# SCH_Portable-PDS-DIMM-Card-Rev-1_1_2026-.net
KiCad netlist of a schematic drawn in EasyEDA
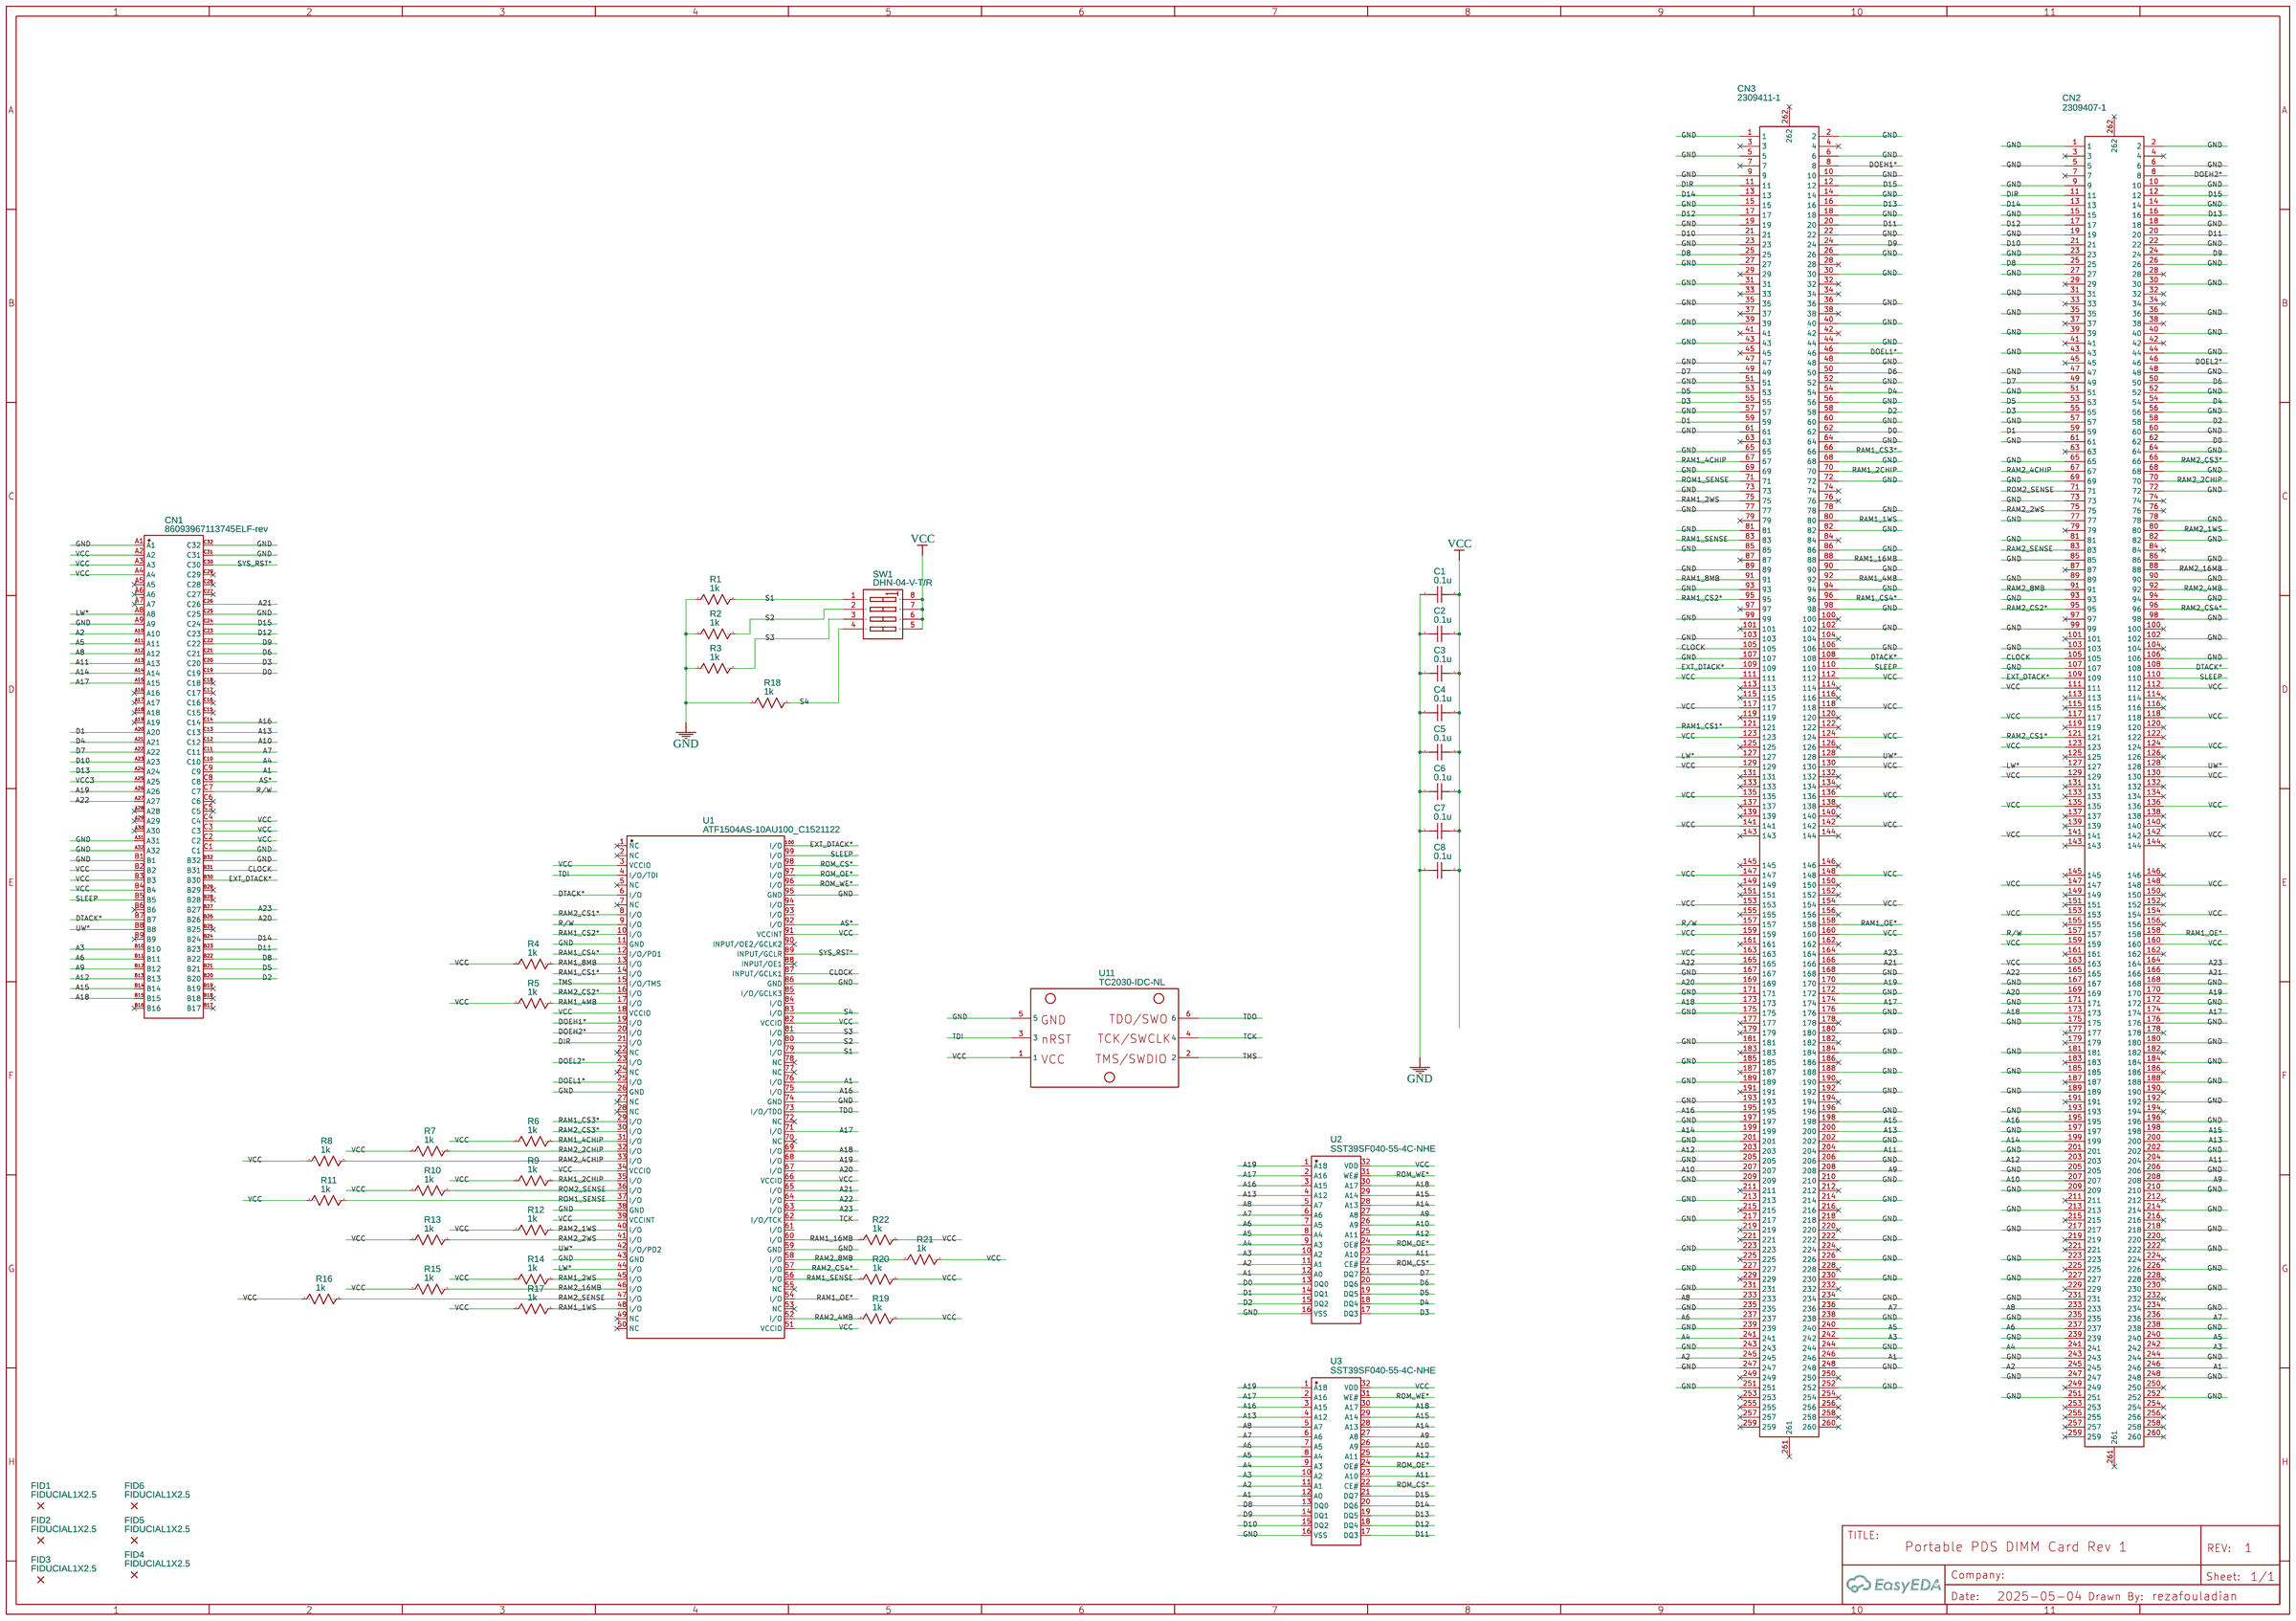
[diagram p0: schematic sheet]

(export (version "E")
  (design (tool "Eeschema 10.0.6"))
  (components
    (comp (ref "C1") (value "0.1u") (libsource (lib "") (part "C_0402_US")))
    (comp (ref "C2") (value "0.1u") (libsource (lib "") (part "C_0402_US")))
    (comp (ref "C3") (value "0.1u") (libsource (lib "") (part "C_0402_US")))
    (comp (ref "C4") (value "0.1u") (libsource (lib "") (part "C_0402_US")))
    (comp (ref "C5") (value "0.1u") (libsource (lib "") (part "C_0402_US")))
    (comp (ref "C6") (value "0.1u") (libsource (lib "") (part "C_0402_US")))
    (comp (ref "C7") (value "0.1u") (libsource (lib "") (part "C_0402_US")))
    (comp (ref "C8") (value "0.1u") (libsource (lib "") (part "C_0402_US")))
    (comp (ref "CN1")
      (value "86093967113745ELF-rev")
      (fields (field (name "Manufacturer Part") "86093967113745ELF") (field (name "Manufacturer") "Amphenol"))
      (libsource (lib "") (part "86093967113745ELF-rev"))
    )
    (comp (ref "CN2")
      (value "2309407-1")
      (fields (field (name "Manufacturer") "TE Connectivity(泰科电子)"))
      (libsource (lib "") (part "2309407-1"))
    )
    (comp (ref "CN3")
      (value "2309411-1")
      (fields (field (name "Manufacturer") "TE Connectivity(泰科电子)"))
      (libsource (lib "") (part "2309411-1"))
    )
    (comp (ref "FID1") (value "FIDUCIAL1X2.5") (libsource (lib "") (part "FIDUCIAL1X2.5")))
    (comp (ref "FID2") (value "FIDUCIAL1X2.5") (libsource (lib "") (part "FIDUCIAL1X2.5")))
    (comp (ref "FID3") (value "FIDUCIAL1X2.5") (libsource (lib "") (part "FIDUCIAL1X2.5")))
    (comp (ref "FID4") (value "FIDUCIAL1X2.5") (libsource (lib "") (part "FIDUCIAL1X2.5")))
    (comp (ref "FID5") (value "FIDUCIAL1X2.5") (libsource (lib "") (part "FIDUCIAL1X2.5")))
    (comp (ref "FID6") (value "FIDUCIAL1X2.5") (libsource (lib "") (part "FIDUCIAL1X2.5")))
    (comp (ref "OSHW")
      (value "OSHWA LOGO")
      (fields (field (name "Manufacturer") "Open Source Hardware Association"))
      (libsource (lib "") (part "OSHWA LOGO"))
    )
    (comp (ref "R1") (value "1k") (libsource (lib "") (part "R_0402_US")))
    (comp (ref "R2") (value "1k") (libsource (lib "") (part "R_0402_US")))
    (comp (ref "R3") (value "1k") (libsource (lib "") (part "R_0402_US")))
    (comp (ref "R4") (value "1k") (libsource (lib "") (part "R_0402_US")))
    (comp (ref "R5") (value "1k") (libsource (lib "") (part "R_0402_US")))
    (comp (ref "R6") (value "1k") (libsource (lib "") (part "R_0402_US")))
    (comp (ref "R7") (value "1k") (libsource (lib "") (part "R_0402_US")))
    (comp (ref "R8") (value "1k") (libsource (lib "") (part "R_0402_US")))
    (comp (ref "R9") (value "1k") (libsource (lib "") (part "R_0402_US")))
    (comp (ref "R10") (value "1k") (libsource (lib "") (part "R_0402_US")))
    (comp (ref "R11") (value "1k") (libsource (lib "") (part "R_0402_US")))
    (comp (ref "R12") (value "1k") (libsource (lib "") (part "R_0402_US")))
    (comp (ref "R13") (value "1k") (libsource (lib "") (part "R_0402_US")))
    (comp (ref "R14") (value "1k") (libsource (lib "") (part "R_0402_US")))
    (comp (ref "R15") (value "1k") (libsource (lib "") (part "R_0402_US")))
    (comp (ref "R16") (value "1k") (libsource (lib "") (part "R_0402_US")))
    (comp (ref "R17") (value "1k") (libsource (lib "") (part "R_0402_US")))
    (comp (ref "R18") (value "1k") (libsource (lib "") (part "R_0402_US")))
    (comp (ref "R19") (value "1k") (libsource (lib "") (part "R_0402_US")))
    (comp (ref "R20") (value "1k") (libsource (lib "") (part "R_0402_US")))
    (comp (ref "R21") (value "1k") (libsource (lib "") (part "R_0402_US")))
    (comp (ref "R22") (value "1k") (libsource (lib "") (part "R_0402_US")))
    (comp (ref "SW1")
      (value "DHN-04-V-T/R")
      (fields (field (name "Manufacturer") "圜达"))
      (libsource (lib "") (part "DHN-04-V-T/R"))
    )
    (comp (ref "U1")
      (value "ATF1504AS-10AU100_C1521122")
      (fields
        (field (name "Manufacturer Part") "ATF1504AS-10AU100")
        (field (name "Manufacturer") "MICROCHIP(美国微芯)")
      )
      (libsource (lib "") (part "ATF1504AS-10AU100_C1521122"))
    )
    (comp (ref "U2")
      (value "SST39SF040-55-4C-NHE")
      (fields (field (name "Manufacturer") "MICROCHIP(美国微芯)"))
      (libsource (lib "") (part "SST39SF040-55-4C-NHE"))
    )
    (comp (ref "U3")
      (value "SST39SF040-55-4C-NHE")
      (fields (field (name "Manufacturer") "MICROCHIP(美国微芯)"))
      (libsource (lib "") (part "SST39SF040-55-4C-NHE"))
    )
    (comp (ref "U11")
      (value "TC2030-IDC-NL")
      (fields (field (name "Manufacturer") "Tag-Connect"))
      (libsource (lib "") (part "TC2030-IDC-NL"))
    )
  )
  (nets
    (net (code "1") (name "/A1") (class "Default")
      (node (ref "CN1") (pin "C9") (pinfunction "C9_C9") (pintype "unspecified"))
      (node (ref "CN2") (pin "246") (pinfunction "246_246") (pintype "unspecified"))
      (node (ref "CN3") (pin "246") (pinfunction "246_246") (pintype "unspecified"))
      (node (ref "U1") (pin "76") (pinfunction "I/O_76") (pintype "unspecified"))
      (node (ref "U2") (pin "12") (pinfunction "A0_12") (pintype "unspecified"))
      (node (ref "U3") (pin "12") (pinfunction "A0_12") (pintype "unspecified"))
    )
    (net (code "2") (name "/A2") (class "Default")
      (node (ref "CN1") (pin "A10") (pinfunction "A10_A10") (pintype "unspecified"))
      (node (ref "CN2") (pin "245") (pinfunction "245_245") (pintype "unspecified"))
      (node (ref "CN3") (pin "245") (pinfunction "245_245") (pintype "unspecified"))
      (node (ref "U2") (pin "11") (pinfunction "A1_11") (pintype "unspecified"))
      (node (ref "U3") (pin "11") (pinfunction "A1_11") (pintype "unspecified"))
    )
    (net (code "3") (name "/A3") (class "Default")
      (node (ref "CN1") (pin "B10") (pinfunction "B10_B10") (pintype "unspecified"))
      (node (ref "CN2") (pin "242") (pinfunction "242_242") (pintype "unspecified"))
      (node (ref "CN3") (pin "242") (pinfunction "242_242") (pintype "unspecified"))
      (node (ref "U2") (pin "10") (pinfunction "A2_10") (pintype "unspecified"))
      (node (ref "U3") (pin "10") (pinfunction "A2_10") (pintype "unspecified"))
    )
    (net (code "4") (name "/A4") (class "Default")
      (node (ref "CN1") (pin "C10") (pinfunction "C10_C10") (pintype "unspecified"))
      (node (ref "CN2") (pin "241") (pinfunction "241_241") (pintype "unspecified"))
      (node (ref "CN3") (pin "241") (pinfunction "241_241") (pintype "unspecified"))
      (node (ref "U2") (pin "9") (pinfunction "A3_9") (pintype "unspecified"))
      (node (ref "U3") (pin "9") (pinfunction "A3_9") (pintype "unspecified"))
    )
    (net (code "5") (name "/A5") (class "Default")
      (node (ref "CN1") (pin "A11") (pinfunction "A11_A11") (pintype "unspecified"))
      (node (ref "CN2") (pin "240") (pinfunction "240_240") (pintype "unspecified"))
      (node (ref "CN3") (pin "240") (pinfunction "240_240") (pintype "unspecified"))
      (node (ref "U2") (pin "8") (pinfunction "A4_8") (pintype "unspecified"))
      (node (ref "U3") (pin "8") (pinfunction "A4_8") (pintype "unspecified"))
    )
    (net (code "6") (name "/A6") (class "Default")
      (node (ref "CN1") (pin "B11") (pinfunction "B11_B11") (pintype "unspecified"))
      (node (ref "CN2") (pin "237") (pinfunction "237_237") (pintype "unspecified"))
      (node (ref "CN3") (pin "237") (pinfunction "237_237") (pintype "unspecified"))
      (node (ref "U2") (pin "7") (pinfunction "A5_7") (pintype "unspecified"))
      (node (ref "U3") (pin "7") (pinfunction "A5_7") (pintype "unspecified"))
    )
    (net (code "7") (name "/A7") (class "Default")
      (node (ref "CN1") (pin "C11") (pinfunction "C11_C11") (pintype "unspecified"))
      (node (ref "CN2") (pin "236") (pinfunction "236_236") (pintype "unspecified"))
      (node (ref "CN3") (pin "236") (pinfunction "236_236") (pintype "unspecified"))
      (node (ref "U2") (pin "6") (pinfunction "A6_6") (pintype "unspecified"))
      (node (ref "U3") (pin "6") (pinfunction "A6_6") (pintype "unspecified"))
    )
    (net (code "8") (name "/A8") (class "Default")
      (node (ref "CN1") (pin "A12") (pinfunction "A12_A12") (pintype "unspecified"))
      (node (ref "CN2") (pin "233") (pinfunction "233_233") (pintype "unspecified"))
      (node (ref "CN3") (pin "233") (pinfunction "233_233") (pintype "unspecified"))
      (node (ref "U2") (pin "5") (pinfunction "A7_5") (pintype "unspecified"))
      (node (ref "U3") (pin "5") (pinfunction "A7_5") (pintype "unspecified"))
    )
    (net (code "9") (name "/A9") (class "Default")
      (node (ref "CN1") (pin "B12") (pinfunction "B12_B12") (pintype "unspecified"))
      (node (ref "CN2") (pin "208") (pinfunction "208_208") (pintype "unspecified"))
      (node (ref "CN3") (pin "208") (pinfunction "208_208") (pintype "unspecified"))
      (node (ref "U2") (pin "27") (pinfunction "A8_27") (pintype "unspecified"))
      (node (ref "U3") (pin "27") (pinfunction "A8_27") (pintype "unspecified"))
    )
    (net (code "10") (name "/A10") (class "Default")
      (node (ref "CN1") (pin "C12") (pinfunction "C12_C12") (pintype "unspecified"))
      (node (ref "CN2") (pin "207") (pinfunction "207_207") (pintype "unspecified"))
      (node (ref "CN3") (pin "207") (pinfunction "207_207") (pintype "unspecified"))
      (node (ref "U2") (pin "26") (pinfunction "A9_26") (pintype "unspecified"))
      (node (ref "U3") (pin "26") (pinfunction "A9_26") (pintype "unspecified"))
    )
    (net (code "11") (name "/A11") (class "Default")
      (node (ref "CN1") (pin "A13") (pinfunction "A13_A13") (pintype "unspecified"))
      (node (ref "CN2") (pin "204") (pinfunction "204_204") (pintype "unspecified"))
      (node (ref "CN3") (pin "204") (pinfunction "204_204") (pintype "unspecified"))
      (node (ref "U2") (pin "23") (pinfunction "A10_23") (pintype "unspecified"))
      (node (ref "U3") (pin "23") (pinfunction "A10_23") (pintype "unspecified"))
    )
    (net (code "12") (name "/A12") (class "Default")
      (node (ref "CN1") (pin "B13") (pinfunction "B13_B13") (pintype "unspecified"))
      (node (ref "CN2") (pin "203") (pinfunction "203_203") (pintype "unspecified"))
      (node (ref "CN3") (pin "203") (pinfunction "203_203") (pintype "unspecified"))
      (node (ref "U2") (pin "25") (pinfunction "A11_25") (pintype "unspecified"))
      (node (ref "U3") (pin "25") (pinfunction "A11_25") (pintype "unspecified"))
    )
    (net (code "13") (name "/A13") (class "Default")
      (node (ref "CN1") (pin "C13") (pinfunction "C13_C13") (pintype "unspecified"))
      (node (ref "CN2") (pin "200") (pinfunction "200_200") (pintype "unspecified"))
      (node (ref "CN3") (pin "200") (pinfunction "200_200") (pintype "unspecified"))
      (node (ref "U2") (pin "4") (pinfunction "A12_4") (pintype "unspecified"))
      (node (ref "U3") (pin "4") (pinfunction "A12_4") (pintype "unspecified"))
    )
    (net (code "14") (name "/A14") (class "Default")
      (node (ref "CN1") (pin "A14") (pinfunction "A14_A14") (pintype "unspecified"))
      (node (ref "CN2") (pin "199") (pinfunction "199_199") (pintype "unspecified"))
      (node (ref "CN3") (pin "199") (pinfunction "199_199") (pintype "unspecified"))
      (node (ref "U2") (pin "28") (pinfunction "A13_28") (pintype "unspecified"))
      (node (ref "U3") (pin "28") (pinfunction "A13_28") (pintype "unspecified"))
    )
    (net (code "15") (name "/A15") (class "Default")
      (node (ref "CN1") (pin "B14") (pinfunction "B14_B14") (pintype "unspecified"))
      (node (ref "CN2") (pin "198") (pinfunction "198_198") (pintype "unspecified"))
      (node (ref "CN3") (pin "198") (pinfunction "198_198") (pintype "unspecified"))
      (node (ref "U2") (pin "29") (pinfunction "A14_29") (pintype "unspecified"))
      (node (ref "U3") (pin "29") (pinfunction "A14_29") (pintype "unspecified"))
    )
    (net (code "16") (name "/A16") (class "Default")
      (node (ref "CN1") (pin "C14") (pinfunction "C14_C14") (pintype "unspecified"))
      (node (ref "CN2") (pin "195") (pinfunction "195_195") (pintype "unspecified"))
      (node (ref "CN3") (pin "195") (pinfunction "195_195") (pintype "unspecified"))
      (node (ref "U1") (pin "75") (pinfunction "I/O_75") (pintype "unspecified"))
      (node (ref "U2") (pin "3") (pinfunction "A15_3") (pintype "unspecified"))
      (node (ref "U3") (pin "3") (pinfunction "A15_3") (pintype "unspecified"))
    )
    (net (code "17") (name "/A17") (class "Default")
      (node (ref "CN1") (pin "A15") (pinfunction "A15_A15") (pintype "unspecified"))
      (node (ref "CN2") (pin "174") (pinfunction "174_174") (pintype "unspecified"))
      (node (ref "CN3") (pin "174") (pinfunction "174_174") (pintype "unspecified"))
      (node (ref "U1") (pin "71") (pinfunction "I/O_71") (pintype "unspecified"))
      (node (ref "U2") (pin "2") (pinfunction "A16_2") (pintype "unspecified"))
      (node (ref "U3") (pin "2") (pinfunction "A16_2") (pintype "unspecified"))
    )
    (net (code "18") (name "/A18") (class "Default")
      (node (ref "CN1") (pin "B15") (pinfunction "B15_B15") (pintype "unspecified"))
      (node (ref "CN2") (pin "173") (pinfunction "173_173") (pintype "unspecified"))
      (node (ref "CN3") (pin "173") (pinfunction "173_173") (pintype "unspecified"))
      (node (ref "U1") (pin "69") (pinfunction "I/O_69") (pintype "unspecified"))
      (node (ref "U2") (pin "30") (pinfunction "A17_30") (pintype "unspecified"))
      (node (ref "U3") (pin "30") (pinfunction "A17_30") (pintype "unspecified"))
    )
    (net (code "19") (name "/A19") (class "Default")
      (node (ref "CN1") (pin "A26") (pinfunction "A26_A26") (pintype "unspecified"))
      (node (ref "CN2") (pin "170") (pinfunction "170_170") (pintype "unspecified"))
      (node (ref "CN3") (pin "170") (pinfunction "170_170") (pintype "unspecified"))
      (node (ref "U1") (pin "68") (pinfunction "I/O_68") (pintype "unspecified"))
      (node (ref "U2") (pin "1") (pinfunction "A18_1") (pintype "unspecified"))
      (node (ref "U3") (pin "1") (pinfunction "A18_1") (pintype "unspecified"))
    )
    (net (code "20") (name "/A20") (class "Default")
      (node (ref "CN1") (pin "B26") (pinfunction "B26_B26") (pintype "unspecified"))
      (node (ref "CN2") (pin "169") (pinfunction "169_169") (pintype "unspecified"))
      (node (ref "CN3") (pin "169") (pinfunction "169_169") (pintype "unspecified"))
      (node (ref "U1") (pin "67") (pinfunction "I/O_67") (pintype "unspecified"))
    )
    (net (code "21") (name "/A21") (class "Default")
      (node (ref "CN1") (pin "C26") (pinfunction "C26_C26") (pintype "unspecified"))
      (node (ref "CN2") (pin "166") (pinfunction "166_166") (pintype "unspecified"))
      (node (ref "CN3") (pin "166") (pinfunction "166_166") (pintype "unspecified"))
      (node (ref "U1") (pin "65") (pinfunction "I/O_65") (pintype "unspecified"))
    )
    (net (code "22") (name "/A22") (class "Default")
      (node (ref "CN1") (pin "A27") (pinfunction "A27_A27") (pintype "unspecified"))
      (node (ref "CN2") (pin "165") (pinfunction "165_165") (pintype "unspecified"))
      (node (ref "CN3") (pin "165") (pinfunction "165_165") (pintype "unspecified"))
      (node (ref "U1") (pin "64") (pinfunction "I/O_64") (pintype "unspecified"))
    )
    (net (code "23") (name "/A23") (class "Default")
      (node (ref "CN1") (pin "B27") (pinfunction "B27_B27") (pintype "unspecified"))
      (node (ref "CN2") (pin "164") (pinfunction "164_164") (pintype "unspecified"))
      (node (ref "CN3") (pin "164") (pinfunction "164_164") (pintype "unspecified"))
      (node (ref "U1") (pin "63") (pinfunction "I/O_63") (pintype "unspecified"))
    )
    (net (code "24") (name "/AS*") (class "Default")
      (node (ref "CN1") (pin "C8") (pinfunction "C8_C8") (pintype "unspecified"))
      (node (ref "U1") (pin "92") (pinfunction "I/O_92") (pintype "unspecified"))
    )
    (net (code "25") (name "/CLOCK") (class "Default")
      (node (ref "CN1") (pin "B31") (pinfunction "B31_B31") (pintype "unspecified"))
      (node (ref "CN2") (pin "105") (pinfunction "105_105") (pintype "unspecified"))
      (node (ref "CN3") (pin "105") (pinfunction "105_105") (pintype "unspecified"))
      (node (ref "U1") (pin "87") (pinfunction "INPUT/GCLK1_87") (pintype "unspecified"))
    )
    (net (code "26") (name "/D0") (class "Default")
      (node (ref "CN1") (pin "C19") (pinfunction "C19_C19") (pintype "unspecified"))
      (node (ref "CN2") (pin "62") (pinfunction "62_62") (pintype "unspecified"))
      (node (ref "CN3") (pin "62") (pinfunction "62_62") (pintype "unspecified"))
      (node (ref "U2") (pin "13") (pinfunction "DQ0_13") (pintype "unspecified"))
    )
    (net (code "27") (name "/D1") (class "Default")
      (node (ref "CN1") (pin "A20") (pinfunction "A20_A20") (pintype "unspecified"))
      (node (ref "CN2") (pin "59") (pinfunction "59_59") (pintype "unspecified"))
      (node (ref "CN3") (pin "59") (pinfunction "59_59") (pintype "unspecified"))
      (node (ref "U2") (pin "14") (pinfunction "DQ1_14") (pintype "unspecified"))
    )
    (net (code "28") (name "/D2") (class "Default")
      (node (ref "CN1") (pin "B20") (pinfunction "B20_B20") (pintype "unspecified"))
      (node (ref "CN2") (pin "58") (pinfunction "58_58") (pintype "unspecified"))
      (node (ref "CN3") (pin "58") (pinfunction "58_58") (pintype "unspecified"))
      (node (ref "U2") (pin "15") (pinfunction "DQ2_15") (pintype "unspecified"))
    )
    (net (code "29") (name "/D3") (class "Default")
      (node (ref "CN1") (pin "C20") (pinfunction "C20_C20") (pintype "unspecified"))
      (node (ref "CN2") (pin "55") (pinfunction "55_55") (pintype "unspecified"))
      (node (ref "CN3") (pin "55") (pinfunction "55_55") (pintype "unspecified"))
      (node (ref "U2") (pin "17") (pinfunction "DQ3_17") (pintype "unspecified"))
    )
    (net (code "30") (name "/D4") (class "Default")
      (node (ref "CN1") (pin "A21") (pinfunction "A21_A21") (pintype "unspecified"))
      (node (ref "CN2") (pin "54") (pinfunction "54_54") (pintype "unspecified"))
      (node (ref "CN3") (pin "54") (pinfunction "54_54") (pintype "unspecified"))
      (node (ref "U2") (pin "18") (pinfunction "DQ4_18") (pintype "unspecified"))
    )
    (net (code "31") (name "/D5") (class "Default")
      (node (ref "CN1") (pin "B21") (pinfunction "B21_B21") (pintype "unspecified"))
      (node (ref "CN2") (pin "53") (pinfunction "53_53") (pintype "unspecified"))
      (node (ref "CN3") (pin "53") (pinfunction "53_53") (pintype "unspecified"))
      (node (ref "U2") (pin "19") (pinfunction "DQ5_19") (pintype "unspecified"))
    )
    (net (code "32") (name "/D6") (class "Default")
      (node (ref "CN1") (pin "C21") (pinfunction "C21_C21") (pintype "unspecified"))
      (node (ref "CN2") (pin "50") (pinfunction "50_50") (pintype "unspecified"))
      (node (ref "CN3") (pin "50") (pinfunction "50_50") (pintype "unspecified"))
      (node (ref "U2") (pin "20") (pinfunction "DQ6_20") (pintype "unspecified"))
    )
    (net (code "33") (name "/D7") (class "Default")
      (node (ref "CN1") (pin "A22") (pinfunction "A22_A22") (pintype "unspecified"))
      (node (ref "CN2") (pin "49") (pinfunction "49_49") (pintype "unspecified"))
      (node (ref "CN3") (pin "49") (pinfunction "49_49") (pintype "unspecified"))
      (node (ref "U2") (pin "21") (pinfunction "DQ7_21") (pintype "unspecified"))
    )
    (net (code "34") (name "/D8") (class "Default")
      (node (ref "CN1") (pin "B22") (pinfunction "B22_B22") (pintype "unspecified"))
      (node (ref "CN2") (pin "25") (pinfunction "25_25") (pintype "unspecified"))
      (node (ref "CN3") (pin "25") (pinfunction "25_25") (pintype "unspecified"))
      (node (ref "U3") (pin "13") (pinfunction "DQ0_13") (pintype "unspecified"))
    )
    (net (code "35") (name "/D9") (class "Default")
      (node (ref "CN1") (pin "C22") (pinfunction "C22_C22") (pintype "unspecified"))
      (node (ref "CN2") (pin "24") (pinfunction "24_24") (pintype "unspecified"))
      (node (ref "CN3") (pin "24") (pinfunction "24_24") (pintype "unspecified"))
      (node (ref "U3") (pin "14") (pinfunction "DQ1_14") (pintype "unspecified"))
    )
    (net (code "36") (name "/D10") (class "Default")
      (node (ref "CN1") (pin "A23") (pinfunction "A23_A23") (pintype "unspecified"))
      (node (ref "CN2") (pin "21") (pinfunction "21_21") (pintype "unspecified"))
      (node (ref "CN3") (pin "21") (pinfunction "21_21") (pintype "unspecified"))
      (node (ref "U3") (pin "15") (pinfunction "DQ2_15") (pintype "unspecified"))
    )
    (net (code "37") (name "/D11") (class "Default")
      (node (ref "CN1") (pin "B23") (pinfunction "B23_B23") (pintype "unspecified"))
      (node (ref "CN2") (pin "20") (pinfunction "20_20") (pintype "unspecified"))
      (node (ref "CN3") (pin "20") (pinfunction "20_20") (pintype "unspecified"))
      (node (ref "U3") (pin "17") (pinfunction "DQ3_17") (pintype "unspecified"))
    )
    (net (code "38") (name "/D12") (class "Default")
      (node (ref "CN1") (pin "C23") (pinfunction "C23_C23") (pintype "unspecified"))
      (node (ref "CN2") (pin "17") (pinfunction "17_17") (pintype "unspecified"))
      (node (ref "CN3") (pin "17") (pinfunction "17_17") (pintype "unspecified"))
      (node (ref "U3") (pin "18") (pinfunction "DQ4_18") (pintype "unspecified"))
    )
    (net (code "39") (name "/D13") (class "Default")
      (node (ref "CN1") (pin "A24") (pinfunction "A24_A24") (pintype "unspecified"))
      (node (ref "CN2") (pin "16") (pinfunction "16_16") (pintype "unspecified"))
      (node (ref "CN3") (pin "16") (pinfunction "16_16") (pintype "unspecified"))
      (node (ref "U3") (pin "19") (pinfunction "DQ5_19") (pintype "unspecified"))
    )
    (net (code "40") (name "/D14") (class "Default")
      (node (ref "CN1") (pin "B24") (pinfunction "B24_B24") (pintype "unspecified"))
      (node (ref "CN2") (pin "13") (pinfunction "13_13") (pintype "unspecified"))
      (node (ref "CN3") (pin "13") (pinfunction "13_13") (pintype "unspecified"))
      (node (ref "U3") (pin "20") (pinfunction "DQ6_20") (pintype "unspecified"))
    )
    (net (code "41") (name "/D15") (class "Default")
      (node (ref "CN1") (pin "C24") (pinfunction "C24_C24") (pintype "unspecified"))
      (node (ref "CN2") (pin "12") (pinfunction "12_12") (pintype "unspecified"))
      (node (ref "CN3") (pin "12") (pinfunction "12_12") (pintype "unspecified"))
      (node (ref "U3") (pin "21") (pinfunction "DQ7_21") (pintype "unspecified"))
    )
    (net (code "42") (name "/DIR") (class "Default")
      (node (ref "CN2") (pin "11") (pinfunction "11_11") (pintype "unspecified"))
      (node (ref "CN3") (pin "11") (pinfunction "11_11") (pintype "unspecified"))
      (node (ref "U1") (pin "21") (pinfunction "I/O_21") (pintype "unspecified"))
    )
    (net (code "43") (name "/DOEH1*") (class "Default")
      (node (ref "CN3") (pin "8") (pinfunction "8_8") (pintype "unspecified"))
      (node (ref "U1") (pin "19") (pinfunction "I/O_19") (pintype "unspecified"))
    )
    (net (code "44") (name "/DOEH2*") (class "Default")
      (node (ref "CN2") (pin "8") (pinfunction "8_8") (pintype "unspecified"))
      (node (ref "U1") (pin "20") (pinfunction "I/O_20") (pintype "unspecified"))
    )
    (net (code "45") (name "/DOEL1*") (class "Default")
      (node (ref "CN3") (pin "46") (pinfunction "46_46") (pintype "unspecified"))
      (node (ref "U1") (pin "25") (pinfunction "I/O_25") (pintype "unspecified"))
    )
    (net (code "46") (name "/DOEL2*") (class "Default")
      (node (ref "CN2") (pin "46") (pinfunction "46_46") (pintype "unspecified"))
      (node (ref "U1") (pin "23") (pinfunction "I/O_23") (pintype "unspecified"))
    )
    (net (code "47") (name "/DTACK*") (class "Default")
      (node (ref "CN1") (pin "B7") (pinfunction "B7_B7") (pintype "unspecified"))
      (node (ref "CN2") (pin "108") (pinfunction "108_108") (pintype "unspecified"))
      (node (ref "CN3") (pin "108") (pinfunction "108_108") (pintype "unspecified"))
      (node (ref "U1") (pin "6") (pinfunction "I/O_6") (pintype "unspecified"))
    )
    (net (code "48") (name "/EXT_DTACK*") (class "Default")
      (node (ref "CN1") (pin "B30") (pinfunction "B30_B30") (pintype "unspecified"))
      (node (ref "CN2") (pin "109") (pinfunction "109_109") (pintype "unspecified"))
      (node (ref "CN3") (pin "109") (pinfunction "109_109") (pintype "unspecified"))
      (node (ref "U1") (pin "100") (pinfunction "I/O_100") (pintype "unspecified"))
    )
    (net (code "49") (name "/LW*") (class "Default")
      (node (ref "CN1") (pin "A8") (pinfunction "A8_A8") (pintype "unspecified"))
      (node (ref "CN2") (pin "127") (pinfunction "127_127") (pintype "unspecified"))
      (node (ref "CN3") (pin "127") (pinfunction "127_127") (pintype "unspecified"))
      (node (ref "U1") (pin "44") (pinfunction "I/O_44") (pintype "unspecified"))
    )
    (net (code "50") (name "/RAM1_1WS") (class "Default")
      (node (ref "CN3") (pin "80") (pinfunction "80_80") (pintype "unspecified"))
      (node (ref "R17") (pin "2") (pinfunction "2_2") (pintype "unspecified"))
      (node (ref "U1") (pin "48") (pinfunction "I/O_48") (pintype "unspecified"))
    )
    (net (code "51") (name "/RAM1_2CHIP") (class "Default")
      (node (ref "CN3") (pin "70") (pinfunction "70_70") (pintype "unspecified"))
      (node (ref "R9") (pin "2") (pinfunction "2_2") (pintype "unspecified"))
      (node (ref "U1") (pin "35") (pinfunction "I/O_35") (pintype "unspecified"))
    )
    (net (code "52") (name "/RAM1_2WS") (class "Default")
      (node (ref "CN3") (pin "75") (pinfunction "75_75") (pintype "unspecified"))
      (node (ref "R14") (pin "2") (pinfunction "2_2") (pintype "unspecified"))
      (node (ref "U1") (pin "45") (pinfunction "I/O_45") (pintype "unspecified"))
    )
    (net (code "53") (name "/RAM1_4CHIP") (class "Default")
      (node (ref "CN3") (pin "67") (pinfunction "67_67") (pintype "unspecified"))
      (node (ref "R6") (pin "2") (pinfunction "2_2") (pintype "unspecified"))
      (node (ref "U1") (pin "31") (pinfunction "I/O_31") (pintype "unspecified"))
    )
    (net (code "54") (name "/RAM1_4MB") (class "Default")
      (node (ref "CN3") (pin "92") (pinfunction "92_92") (pintype "unspecified"))
      (node (ref "R5") (pin "2") (pinfunction "2_2") (pintype "unspecified"))
      (node (ref "U1") (pin "17") (pinfunction "I/O_17") (pintype "unspecified"))
    )
    (net (code "55") (name "/RAM1_8MB") (class "Default")
      (node (ref "CN3") (pin "91") (pinfunction "91_91") (pintype "unspecified"))
      (node (ref "R4") (pin "2") (pinfunction "2_2") (pintype "unspecified"))
      (node (ref "U1") (pin "13") (pinfunction "I/O_13") (pintype "unspecified"))
    )
    (net (code "56") (name "/RAM1_16MB") (class "Default")
      (node (ref "CN3") (pin "88") (pinfunction "88_88") (pintype "unspecified"))
      (node (ref "R22") (pin "1") (pinfunction "1_1") (pintype "unspecified"))
      (node (ref "U1") (pin "60") (pinfunction "I/O_60") (pintype "unspecified"))
    )
    (net (code "57") (name "/RAM1_CS1*") (class "Default")
      (node (ref "CN3") (pin "121") (pinfunction "121_121") (pintype "unspecified"))
      (node (ref "U1") (pin "14") (pinfunction "I/O_14") (pintype "unspecified"))
    )
    (net (code "58") (name "/RAM1_CS2*") (class "Default")
      (node (ref "CN3") (pin "95") (pinfunction "95_95") (pintype "unspecified"))
      (node (ref "U1") (pin "10") (pinfunction "I/O_10") (pintype "unspecified"))
    )
    (net (code "59") (name "/RAM1_CS3*") (class "Default")
      (node (ref "CN3") (pin "66") (pinfunction "66_66") (pintype "unspecified"))
      (node (ref "U1") (pin "29") (pinfunction "I/O_29") (pintype "unspecified"))
    )
    (net (code "60") (name "/RAM1_CS4*") (class "Default")
      (node (ref "CN3") (pin "96") (pinfunction "96_96") (pintype "unspecified"))
      (node (ref "U1") (pin "12") (pinfunction "I/O/PD1_12") (pintype "unspecified"))
    )
    (net (code "61") (name "/RAM1_OE*") (class "Default")
      (node (ref "CN2") (pin "158") (pinfunction "158_158") (pintype "unspecified"))
      (node (ref "CN3") (pin "158") (pinfunction "158_158") (pintype "unspecified"))
      (node (ref "U1") (pin "54") (pinfunction "I/O_54") (pintype "unspecified"))
    )
    (net (code "62") (name "/RAM1_SENSE") (class "Default")
      (node (ref "CN3") (pin "83") (pinfunction "83_83") (pintype "unspecified"))
      (node (ref "R20") (pin "1") (pinfunction "1_1") (pintype "unspecified"))
      (node (ref "U1") (pin "56") (pinfunction "I/O_56") (pintype "unspecified"))
    )
    (net (code "63") (name "/RAM2_1WS") (class "Default")
      (node (ref "CN2") (pin "80") (pinfunction "80_80") (pintype "unspecified"))
      (node (ref "R12") (pin "2") (pinfunction "2_2") (pintype "unspecified"))
      (node (ref "U1") (pin "40") (pinfunction "I/O_40") (pintype "unspecified"))
    )
    (net (code "64") (name "/RAM2_2CHIP") (class "Default")
      (node (ref "CN2") (pin "70") (pinfunction "70_70") (pintype "unspecified"))
      (node (ref "R7") (pin "2") (pinfunction "2_2") (pintype "unspecified"))
      (node (ref "U1") (pin "32") (pinfunction "I/O_32") (pintype "unspecified"))
    )
    (net (code "65") (name "/RAM2_2WS") (class "Default")
      (node (ref "CN2") (pin "75") (pinfunction "75_75") (pintype "unspecified"))
      (node (ref "R13") (pin "2") (pinfunction "2_2") (pintype "unspecified"))
      (node (ref "U1") (pin "41") (pinfunction "I/O_41") (pintype "unspecified"))
    )
    (net (code "66") (name "/RAM2_4CHIP") (class "Default")
      (node (ref "CN2") (pin "67") (pinfunction "67_67") (pintype "unspecified"))
      (node (ref "R8") (pin "2") (pinfunction "2_2") (pintype "unspecified"))
      (node (ref "U1") (pin "33") (pinfunction "I/O_33") (pintype "unspecified"))
    )
    (net (code "67") (name "/RAM2_4MB") (class "Default")
      (node (ref "CN2") (pin "92") (pinfunction "92_92") (pintype "unspecified"))
      (node (ref "R19") (pin "1") (pinfunction "1_1") (pintype "unspecified"))
      (node (ref "U1") (pin "52") (pinfunction "I/O_52") (pintype "unspecified"))
    )
    (net (code "68") (name "/RAM2_8MB") (class "Default")
      (node (ref "CN2") (pin "91") (pinfunction "91_91") (pintype "unspecified"))
      (node (ref "R21") (pin "1") (pinfunction "1_1") (pintype "unspecified"))
      (node (ref "U1") (pin "58") (pinfunction "I/O_58") (pintype "unspecified"))
    )
    (net (code "69") (name "/RAM2_16MB") (class "Default")
      (node (ref "CN2") (pin "88") (pinfunction "88_88") (pintype "unspecified"))
      (node (ref "R15") (pin "2") (pinfunction "2_2") (pintype "unspecified"))
      (node (ref "U1") (pin "46") (pinfunction "I/O_46") (pintype "unspecified"))
    )
    (net (code "70") (name "/RAM2_CS1*") (class "Default")
      (node (ref "CN2") (pin "121") (pinfunction "121_121") (pintype "unspecified"))
      (node (ref "U1") (pin "8") (pinfunction "I/O_8") (pintype "unspecified"))
    )
    (net (code "71") (name "/RAM2_CS2*") (class "Default")
      (node (ref "CN2") (pin "95") (pinfunction "95_95") (pintype "unspecified"))
      (node (ref "U1") (pin "16") (pinfunction "I/O_16") (pintype "unspecified"))
    )
    (net (code "72") (name "/RAM2_CS3*") (class "Default")
      (node (ref "CN2") (pin "66") (pinfunction "66_66") (pintype "unspecified"))
      (node (ref "U1") (pin "30") (pinfunction "I/O_30") (pintype "unspecified"))
    )
    (net (code "73") (name "/RAM2_CS4*") (class "Default")
      (node (ref "CN2") (pin "96") (pinfunction "96_96") (pintype "unspecified"))
      (node (ref "U1") (pin "57") (pinfunction "I/O_57") (pintype "unspecified"))
    )
    (net (code "74") (name "/RAM2_SENSE") (class "Default")
      (node (ref "CN2") (pin "83") (pinfunction "83_83") (pintype "unspecified"))
      (node (ref "R16") (pin "2") (pinfunction "2_2") (pintype "unspecified"))
      (node (ref "U1") (pin "47") (pinfunction "I/O_47") (pintype "unspecified"))
    )
    (net (code "75") (name "/ROM1_SENSE") (class "Default")
      (node (ref "CN3") (pin "71") (pinfunction "71_71") (pintype "unspecified"))
      (node (ref "R11") (pin "2") (pinfunction "2_2") (pintype "unspecified"))
      (node (ref "U1") (pin "37") (pinfunction "I/O_37") (pintype "unspecified"))
    )
    (net (code "76") (name "/ROM2_SENSE") (class "Default")
      (node (ref "CN2") (pin "71") (pinfunction "71_71") (pintype "unspecified"))
      (node (ref "R10") (pin "2") (pinfunction "2_2") (pintype "unspecified"))
      (node (ref "U1") (pin "36") (pinfunction "I/O_36") (pintype "unspecified"))
    )
    (net (code "77") (name "/ROM_CS*") (class "Default")
      (node (ref "U1") (pin "98") (pinfunction "I/O_98") (pintype "unspecified"))
      (node (ref "U2") (pin "22") (pinfunction "CE#_22") (pintype "unspecified"))
      (node (ref "U3") (pin "22") (pinfunction "CE#_22") (pintype "unspecified"))
    )
    (net (code "78") (name "/ROM_OE*") (class "Default")
      (node (ref "U1") (pin "97") (pinfunction "I/O_97") (pintype "unspecified"))
      (node (ref "U2") (pin "24") (pinfunction "OE#_24") (pintype "unspecified"))
      (node (ref "U3") (pin "24") (pinfunction "OE#_24") (pintype "unspecified"))
    )
    (net (code "79") (name "/ROM_WE*") (class "Default")
      (node (ref "U1") (pin "96") (pinfunction "I/O_96") (pintype "unspecified"))
      (node (ref "U2") (pin "31") (pinfunction "WE#_31") (pintype "unspecified"))
      (node (ref "U3") (pin "31") (pinfunction "WE#_31") (pintype "unspecified"))
    )
    (net (code "80") (name "/R{slash}W") (class "Default")
      (node (ref "CN1") (pin "C7") (pinfunction "C7_C7") (pintype "unspecified"))
      (node (ref "CN2") (pin "157") (pinfunction "157_157") (pintype "unspecified"))
      (node (ref "CN3") (pin "157") (pinfunction "157_157") (pintype "unspecified"))
      (node (ref "U1") (pin "9") (pinfunction "I/O_9") (pintype "unspecified"))
    )
    (net (code "81") (name "/S1") (class "Default")
      (node (ref "R1") (pin "2") (pinfunction "2_2") (pintype "unspecified"))
      (node (ref "SW1") (pin "1") (pinfunction "A1_1") (pintype "input"))
      (node (ref "U1") (pin "79") (pinfunction "I/O_79") (pintype "unspecified"))
    )
    (net (code "82") (name "/S2") (class "Default")
      (node (ref "R2") (pin "2") (pinfunction "2_2") (pintype "unspecified"))
      (node (ref "SW1") (pin "2") (pinfunction "A2_2") (pintype "input"))
      (node (ref "U1") (pin "80") (pinfunction "I/O_80") (pintype "unspecified"))
    )
    (net (code "83") (name "/S3") (class "Default")
      (node (ref "R3") (pin "2") (pinfunction "2_2") (pintype "unspecified"))
      (node (ref "SW1") (pin "3") (pinfunction "A3_3") (pintype "input"))
      (node (ref "U1") (pin "81") (pinfunction "I/O_81") (pintype "unspecified"))
    )
    (net (code "84") (name "/S4") (class "Default")
      (node (ref "R18") (pin "2") (pinfunction "2_2") (pintype "unspecified"))
      (node (ref "SW1") (pin "4") (pinfunction "A4_4") (pintype "input"))
      (node (ref "U1") (pin "83") (pinfunction "I/O_83") (pintype "unspecified"))
    )
    (net (code "85") (name "/SLEEP") (class "Default")
      (node (ref "CN1") (pin "B5") (pinfunction "B5_B5") (pintype "unspecified"))
      (node (ref "CN2") (pin "110") (pinfunction "110_110") (pintype "unspecified"))
      (node (ref "CN3") (pin "110") (pinfunction "110_110") (pintype "unspecified"))
      (node (ref "U1") (pin "99") (pinfunction "I/O_99") (pintype "unspecified"))
    )
    (net (code "86") (name "/SYS_RST*") (class "Default")
      (node (ref "CN1") (pin "C30") (pinfunction "C30_C30") (pintype "unspecified"))
      (node (ref "U1") (pin "89") (pinfunction "INPUT/GCLR_89") (pintype "unspecified"))
    )
    (net (code "87") (name "/TCK") (class "Default")
      (node (ref "U1") (pin "62") (pinfunction "I/O/TCK_62") (pintype "unspecified"))
      (node (ref "U11") (pin "4") (pinfunction "4_4") (pintype "unspecified"))
    )
    (net (code "88") (name "/TDI") (class "Default")
      (node (ref "U1") (pin "4") (pinfunction "I/O/TDI_4") (pintype "unspecified"))
      (node (ref "U11") (pin "3") (pinfunction "3_3") (pintype "unspecified"))
    )
    (net (code "89") (name "/TDO") (class "Default")
      (node (ref "U1") (pin "73") (pinfunction "I/O/TDO_73") (pintype "unspecified"))
      (node (ref "U11") (pin "6") (pinfunction "6_6") (pintype "unspecified"))
    )
    (net (code "90") (name "/TMS") (class "Default")
      (node (ref "U1") (pin "15") (pinfunction "I/O/TMS_15") (pintype "unspecified"))
      (node (ref "U11") (pin "2") (pinfunction "2_2") (pintype "unspecified"))
    )
    (net (code "91") (name "/UW*") (class "Default")
      (node (ref "CN1") (pin "B8") (pinfunction "B8_B8") (pintype "unspecified"))
      (node (ref "CN2") (pin "128") (pinfunction "128_128") (pintype "unspecified"))
      (node (ref "CN3") (pin "128") (pinfunction "128_128") (pintype "unspecified"))
      (node (ref "U1") (pin "42") (pinfunction "I/O/PD2_42") (pintype "unspecified"))
    )
    (net (code "92") (name "/VCC3") (class "Default")
      (node (ref "CN1") (pin "A25") (pinfunction "A25_A25") (pintype "unspecified"))
    )
    (net (code "93") (name "GND") (class "Default")
      (node (ref "C1") (pin "1") (pinfunction "1_1") (pintype "unspecified"))
      (node (ref "C2") (pin "1") (pinfunction "1_1") (pintype "unspecified"))
      (node (ref "C3") (pin "1") (pinfunction "1_1") (pintype "unspecified"))
      (node (ref "C4") (pin "1") (pinfunction "1_1") (pintype "unspecified"))
      (node (ref "C5") (pin "1") (pinfunction "1_1") (pintype "unspecified"))
      (node (ref "C6") (pin "1") (pinfunction "1_1") (pintype "unspecified"))
      (node (ref "C7") (pin "1") (pinfunction "1_1") (pintype "unspecified"))
      (node (ref "C8") (pin "1") (pinfunction "1_1") (pintype "unspecified"))
      (node (ref "CN1") (pin "A1") (pinfunction "A1_A1") (pintype "unspecified"))
      (node (ref "CN1") (pin "A31") (pinfunction "A31_A31") (pintype "unspecified"))
      (node (ref "CN1") (pin "A32") (pinfunction "A32_A32") (pintype "unspecified"))
      (node (ref "CN1") (pin "A9") (pinfunction "A9_A9") (pintype "unspecified"))
      (node (ref "CN1") (pin "B1") (pinfunction "B1_B1") (pintype "unspecified"))
      (node (ref "CN1") (pin "B32") (pinfunction "B32_B32") (pintype "unspecified"))
      (node (ref "CN1") (pin "C1") (pinfunction "C1_C1") (pintype "unspecified"))
      (node (ref "CN1") (pin "C25") (pinfunction "C25_C25") (pintype "unspecified"))
      (node (ref "CN1") (pin "C31") (pinfunction "C31_C31") (pintype "unspecified"))
      (node (ref "CN1") (pin "C32") (pinfunction "C32_C32") (pintype "unspecified"))
      (node (ref "CN2") (pin "1") (pinfunction "1_1") (pintype "unspecified"))
      (node (ref "CN2") (pin "10") (pinfunction "10_10") (pintype "unspecified"))
      (node (ref "CN2") (pin "102") (pinfunction "102_102") (pintype "unspecified"))
      (node (ref "CN2") (pin "103") (pinfunction "103_103") (pintype "unspecified"))
      (node (ref "CN2") (pin "106") (pinfunction "106_106") (pintype "unspecified"))
      (node (ref "CN2") (pin "107") (pinfunction "107_107") (pintype "unspecified"))
      (node (ref "CN2") (pin "14") (pinfunction "14_14") (pintype "unspecified"))
      (node (ref "CN2") (pin "15") (pinfunction "15_15") (pintype "unspecified"))
      (node (ref "CN2") (pin "167") (pinfunction "167_167") (pintype "unspecified"))
      (node (ref "CN2") (pin "168") (pinfunction "168_168") (pintype "unspecified"))
      (node (ref "CN2") (pin "171") (pinfunction "171_171") (pintype "unspecified"))
      (node (ref "CN2") (pin "172") (pinfunction "172_172") (pintype "unspecified"))
      (node (ref "CN2") (pin "175") (pinfunction "175_175") (pintype "unspecified"))
      (node (ref "CN2") (pin "176") (pinfunction "176_176") (pintype "unspecified"))
      (node (ref "CN2") (pin "18") (pinfunction "18_18") (pintype "unspecified"))
      (node (ref "CN2") (pin "180") (pinfunction "180_180") (pintype "unspecified"))
      (node (ref "CN2") (pin "181") (pinfunction "181_181") (pintype "unspecified"))
      (node (ref "CN2") (pin "184") (pinfunction "184_184") (pintype "unspecified"))
      (node (ref "CN2") (pin "185") (pinfunction "185_185") (pintype "unspecified"))
      (node (ref "CN2") (pin "188") (pinfunction "188_188") (pintype "unspecified"))
      (node (ref "CN2") (pin "189") (pinfunction "189_189") (pintype "unspecified"))
      (node (ref "CN2") (pin "19") (pinfunction "19_19") (pintype "unspecified"))
      (node (ref "CN2") (pin "192") (pinfunction "192_192") (pintype "unspecified"))
      (node (ref "CN2") (pin "193") (pinfunction "193_193") (pintype "unspecified"))
      (node (ref "CN2") (pin "196") (pinfunction "196_196") (pintype "unspecified"))
      (node (ref "CN2") (pin "197") (pinfunction "197_197") (pintype "unspecified"))
      (node (ref "CN2") (pin "2") (pinfunction "2_2") (pintype "unspecified"))
      (node (ref "CN2") (pin "201") (pinfunction "201_201") (pintype "unspecified"))
      (node (ref "CN2") (pin "202") (pinfunction "202_202") (pintype "unspecified"))
      (node (ref "CN2") (pin "205") (pinfunction "205_205") (pintype "unspecified"))
      (node (ref "CN2") (pin "206") (pinfunction "206_206") (pintype "unspecified"))
      (node (ref "CN2") (pin "209") (pinfunction "209_209") (pintype "unspecified"))
      (node (ref "CN2") (pin "210") (pinfunction "210_210") (pintype "unspecified"))
      (node (ref "CN2") (pin "213") (pinfunction "213_213") (pintype "unspecified"))
      (node (ref "CN2") (pin "214") (pinfunction "214_214") (pintype "unspecified"))
      (node (ref "CN2") (pin "217") (pinfunction "217_217") (pintype "unspecified"))
      (node (ref "CN2") (pin "218") (pinfunction "218_218") (pintype "unspecified"))
      (node (ref "CN2") (pin "22") (pinfunction "22_22") (pintype "unspecified"))
      (node (ref "CN2") (pin "222") (pinfunction "222_222") (pintype "unspecified"))
      (node (ref "CN2") (pin "223") (pinfunction "223_223") (pintype "unspecified"))
      (node (ref "CN2") (pin "226") (pinfunction "226_226") (pintype "unspecified"))
      (node (ref "CN2") (pin "227") (pinfunction "227_227") (pintype "unspecified"))
      (node (ref "CN2") (pin "23") (pinfunction "23_23") (pintype "unspecified"))
      (node (ref "CN2") (pin "230") (pinfunction "230_230") (pintype "unspecified"))
      (node (ref "CN2") (pin "231") (pinfunction "231_231") (pintype "unspecified"))
      (node (ref "CN2") (pin "234") (pinfunction "234_234") (pintype "unspecified"))
      (node (ref "CN2") (pin "235") (pinfunction "235_235") (pintype "unspecified"))
      (node (ref "CN2") (pin "238") (pinfunction "238_238") (pintype "unspecified"))
      (node (ref "CN2") (pin "239") (pinfunction "239_239") (pintype "unspecified"))
      (node (ref "CN2") (pin "243") (pinfunction "243_243") (pintype "unspecified"))
      (node (ref "CN2") (pin "244") (pinfunction "244_244") (pintype "unspecified"))
      (node (ref "CN2") (pin "247") (pinfunction "247_247") (pintype "unspecified"))
      (node (ref "CN2") (pin "248") (pinfunction "248_248") (pintype "unspecified"))
      (node (ref "CN2") (pin "251") (pinfunction "251_251") (pintype "unspecified"))
      (node (ref "CN2") (pin "252") (pinfunction "252_252") (pintype "unspecified"))
      (node (ref "CN2") (pin "26") (pinfunction "26_26") (pintype "unspecified"))
      (node (ref "CN2") (pin "27") (pinfunction "27_27") (pintype "unspecified"))
      (node (ref "CN2") (pin "30") (pinfunction "30_30") (pintype "unspecified"))
      (node (ref "CN2") (pin "31") (pinfunction "31_31") (pintype "unspecified"))
      (node (ref "CN2") (pin "35") (pinfunction "35_35") (pintype "unspecified"))
      (node (ref "CN2") (pin "36") (pinfunction "36_36") (pintype "unspecified"))
      (node (ref "CN2") (pin "39") (pinfunction "39_39") (pintype "unspecified"))
      (node (ref "CN2") (pin "40") (pinfunction "40_40") (pintype "unspecified"))
      (node (ref "CN2") (pin "43") (pinfunction "43_43") (pintype "unspecified"))
      (node (ref "CN2") (pin "44") (pinfunction "44_44") (pintype "unspecified"))
      (node (ref "CN2") (pin "47") (pinfunction "47_47") (pintype "unspecified"))
      (node (ref "CN2") (pin "48") (pinfunction "48_48") (pintype "unspecified"))
      (node (ref "CN2") (pin "5") (pinfunction "5_5") (pintype "unspecified"))
      (node (ref "CN2") (pin "51") (pinfunction "51_51") (pintype "unspecified"))
      (node (ref "CN2") (pin "52") (pinfunction "52_52") (pintype "unspecified"))
      (node (ref "CN2") (pin "56") (pinfunction "56_56") (pintype "unspecified"))
      (node (ref "CN2") (pin "57") (pinfunction "57_57") (pintype "unspecified"))
      (node (ref "CN2") (pin "6") (pinfunction "6_6") (pintype "unspecified"))
      (node (ref "CN2") (pin "60") (pinfunction "60_60") (pintype "unspecified"))
      (node (ref "CN2") (pin "61") (pinfunction "61_61") (pintype "unspecified"))
      (node (ref "CN2") (pin "64") (pinfunction "64_64") (pintype "unspecified"))
      (node (ref "CN2") (pin "65") (pinfunction "65_65") (pintype "unspecified"))
      (node (ref "CN2") (pin "68") (pinfunction "68_68") (pintype "unspecified"))
      (node (ref "CN2") (pin "69") (pinfunction "69_69") (pintype "unspecified"))
      (node (ref "CN2") (pin "72") (pinfunction "72_72") (pintype "unspecified"))
      (node (ref "CN2") (pin "73") (pinfunction "73_73") (pintype "unspecified"))
      (node (ref "CN2") (pin "77") (pinfunction "77_77") (pintype "unspecified"))
      (node (ref "CN2") (pin "78") (pinfunction "78_78") (pintype "unspecified"))
      (node (ref "CN2") (pin "81") (pinfunction "81_81") (pintype "unspecified"))
      (node (ref "CN2") (pin "82") (pinfunction "82_82") (pintype "unspecified"))
      (node (ref "CN2") (pin "85") (pinfunction "85_85") (pintype "unspecified"))
      (node (ref "CN2") (pin "86") (pinfunction "86_86") (pintype "unspecified"))
      (node (ref "CN2") (pin "89") (pinfunction "89_89") (pintype "unspecified"))
      (node (ref "CN2") (pin "9") (pinfunction "9_9") (pintype "unspecified"))
      (node (ref "CN2") (pin "90") (pinfunction "90_90") (pintype "unspecified"))
      (node (ref "CN2") (pin "93") (pinfunction "93_93") (pintype "unspecified"))
      (node (ref "CN2") (pin "94") (pinfunction "94_94") (pintype "unspecified"))
      (node (ref "CN2") (pin "98") (pinfunction "98_98") (pintype "unspecified"))
      (node (ref "CN2") (pin "99") (pinfunction "99_99") (pintype "unspecified"))
      (node (ref "CN3") (pin "1") (pinfunction "1_1") (pintype "unspecified"))
      (node (ref "CN3") (pin "10") (pinfunction "10_10") (pintype "unspecified"))
      (node (ref "CN3") (pin "102") (pinfunction "102_102") (pintype "unspecified"))
      (node (ref "CN3") (pin "103") (pinfunction "103_103") (pintype "unspecified"))
      (node (ref "CN3") (pin "106") (pinfunction "106_106") (pintype "unspecified"))
      (node (ref "CN3") (pin "107") (pinfunction "107_107") (pintype "unspecified"))
      (node (ref "CN3") (pin "14") (pinfunction "14_14") (pintype "unspecified"))
      (node (ref "CN3") (pin "15") (pinfunction "15_15") (pintype "unspecified"))
      (node (ref "CN3") (pin "167") (pinfunction "167_167") (pintype "unspecified"))
      (node (ref "CN3") (pin "168") (pinfunction "168_168") (pintype "unspecified"))
      (node (ref "CN3") (pin "171") (pinfunction "171_171") (pintype "unspecified"))
      (node (ref "CN3") (pin "172") (pinfunction "172_172") (pintype "unspecified"))
      (node (ref "CN3") (pin "175") (pinfunction "175_175") (pintype "unspecified"))
      (node (ref "CN3") (pin "176") (pinfunction "176_176") (pintype "unspecified"))
      (node (ref "CN3") (pin "18") (pinfunction "18_18") (pintype "unspecified"))
      (node (ref "CN3") (pin "180") (pinfunction "180_180") (pintype "unspecified"))
      (node (ref "CN3") (pin "181") (pinfunction "181_181") (pintype "unspecified"))
      (node (ref "CN3") (pin "184") (pinfunction "184_184") (pintype "unspecified"))
      (node (ref "CN3") (pin "185") (pinfunction "185_185") (pintype "unspecified"))
      (node (ref "CN3") (pin "188") (pinfunction "188_188") (pintype "unspecified"))
      (node (ref "CN3") (pin "189") (pinfunction "189_189") (pintype "unspecified"))
      (node (ref "CN3") (pin "19") (pinfunction "19_19") (pintype "unspecified"))
      (node (ref "CN3") (pin "192") (pinfunction "192_192") (pintype "unspecified"))
      (node (ref "CN3") (pin "193") (pinfunction "193_193") (pintype "unspecified"))
      (node (ref "CN3") (pin "196") (pinfunction "196_196") (pintype "unspecified"))
      (node (ref "CN3") (pin "197") (pinfunction "197_197") (pintype "unspecified"))
      (node (ref "CN3") (pin "2") (pinfunction "2_2") (pintype "unspecified"))
      (node (ref "CN3") (pin "201") (pinfunction "201_201") (pintype "unspecified"))
      (node (ref "CN3") (pin "202") (pinfunction "202_202") (pintype "unspecified"))
      (node (ref "CN3") (pin "205") (pinfunction "205_205") (pintype "unspecified"))
      (node (ref "CN3") (pin "206") (pinfunction "206_206") (pintype "unspecified"))
      (node (ref "CN3") (pin "209") (pinfunction "209_209") (pintype "unspecified"))
      (node (ref "CN3") (pin "210") (pinfunction "210_210") (pintype "unspecified"))
      (node (ref "CN3") (pin "213") (pinfunction "213_213") (pintype "unspecified"))
      (node (ref "CN3") (pin "214") (pinfunction "214_214") (pintype "unspecified"))
      (node (ref "CN3") (pin "217") (pinfunction "217_217") (pintype "unspecified"))
      (node (ref "CN3") (pin "218") (pinfunction "218_218") (pintype "unspecified"))
      (node (ref "CN3") (pin "22") (pinfunction "22_22") (pintype "unspecified"))
      (node (ref "CN3") (pin "222") (pinfunction "222_222") (pintype "unspecified"))
      (node (ref "CN3") (pin "223") (pinfunction "223_223") (pintype "unspecified"))
      (node (ref "CN3") (pin "226") (pinfunction "226_226") (pintype "unspecified"))
      (node (ref "CN3") (pin "227") (pinfunction "227_227") (pintype "unspecified"))
      (node (ref "CN3") (pin "23") (pinfunction "23_23") (pintype "unspecified"))
      (node (ref "CN3") (pin "230") (pinfunction "230_230") (pintype "unspecified"))
      (node (ref "CN3") (pin "231") (pinfunction "231_231") (pintype "unspecified"))
      (node (ref "CN3") (pin "234") (pinfunction "234_234") (pintype "unspecified"))
      (node (ref "CN3") (pin "235") (pinfunction "235_235") (pintype "unspecified"))
      (node (ref "CN3") (pin "238") (pinfunction "238_238") (pintype "unspecified"))
      (node (ref "CN3") (pin "239") (pinfunction "239_239") (pintype "unspecified"))
      (node (ref "CN3") (pin "243") (pinfunction "243_243") (pintype "unspecified"))
      (node (ref "CN3") (pin "244") (pinfunction "244_244") (pintype "unspecified"))
      (node (ref "CN3") (pin "247") (pinfunction "247_247") (pintype "unspecified"))
      (node (ref "CN3") (pin "248") (pinfunction "248_248") (pintype "unspecified"))
      (node (ref "CN3") (pin "251") (pinfunction "251_251") (pintype "unspecified"))
      (node (ref "CN3") (pin "252") (pinfunction "252_252") (pintype "unspecified"))
      (node (ref "CN3") (pin "26") (pinfunction "26_26") (pintype "unspecified"))
      (node (ref "CN3") (pin "27") (pinfunction "27_27") (pintype "unspecified"))
      (node (ref "CN3") (pin "30") (pinfunction "30_30") (pintype "unspecified"))
      (node (ref "CN3") (pin "31") (pinfunction "31_31") (pintype "unspecified"))
      (node (ref "CN3") (pin "35") (pinfunction "35_35") (pintype "unspecified"))
      (node (ref "CN3") (pin "36") (pinfunction "36_36") (pintype "unspecified"))
      (node (ref "CN3") (pin "39") (pinfunction "39_39") (pintype "unspecified"))
      (node (ref "CN3") (pin "40") (pinfunction "40_40") (pintype "unspecified"))
      (node (ref "CN3") (pin "43") (pinfunction "43_43") (pintype "unspecified"))
      (node (ref "CN3") (pin "44") (pinfunction "44_44") (pintype "unspecified"))
      (node (ref "CN3") (pin "47") (pinfunction "47_47") (pintype "unspecified"))
      (node (ref "CN3") (pin "48") (pinfunction "48_48") (pintype "unspecified"))
      (node (ref "CN3") (pin "5") (pinfunction "5_5") (pintype "unspecified"))
      (node (ref "CN3") (pin "51") (pinfunction "51_51") (pintype "unspecified"))
      (node (ref "CN3") (pin "52") (pinfunction "52_52") (pintype "unspecified"))
      (node (ref "CN3") (pin "56") (pinfunction "56_56") (pintype "unspecified"))
      (node (ref "CN3") (pin "57") (pinfunction "57_57") (pintype "unspecified"))
      (node (ref "CN3") (pin "6") (pinfunction "6_6") (pintype "unspecified"))
      (node (ref "CN3") (pin "60") (pinfunction "60_60") (pintype "unspecified"))
      (node (ref "CN3") (pin "61") (pinfunction "61_61") (pintype "unspecified"))
      (node (ref "CN3") (pin "64") (pinfunction "64_64") (pintype "unspecified"))
      (node (ref "CN3") (pin "65") (pinfunction "65_65") (pintype "unspecified"))
      (node (ref "CN3") (pin "68") (pinfunction "68_68") (pintype "unspecified"))
      (node (ref "CN3") (pin "69") (pinfunction "69_69") (pintype "unspecified"))
      (node (ref "CN3") (pin "72") (pinfunction "72_72") (pintype "unspecified"))
      (node (ref "CN3") (pin "73") (pinfunction "73_73") (pintype "unspecified"))
      (node (ref "CN3") (pin "77") (pinfunction "77_77") (pintype "unspecified"))
      (node (ref "CN3") (pin "78") (pinfunction "78_78") (pintype "unspecified"))
      (node (ref "CN3") (pin "81") (pinfunction "81_81") (pintype "unspecified"))
      (node (ref "CN3") (pin "82") (pinfunction "82_82") (pintype "unspecified"))
      (node (ref "CN3") (pin "85") (pinfunction "85_85") (pintype "unspecified"))
      (node (ref "CN3") (pin "86") (pinfunction "86_86") (pintype "unspecified"))
      (node (ref "CN3") (pin "89") (pinfunction "89_89") (pintype "unspecified"))
      (node (ref "CN3") (pin "9") (pinfunction "9_9") (pintype "unspecified"))
      (node (ref "CN3") (pin "90") (pinfunction "90_90") (pintype "unspecified"))
      (node (ref "CN3") (pin "93") (pinfunction "93_93") (pintype "unspecified"))
      (node (ref "CN3") (pin "94") (pinfunction "94_94") (pintype "unspecified"))
      (node (ref "CN3") (pin "98") (pinfunction "98_98") (pintype "unspecified"))
      (node (ref "CN3") (pin "99") (pinfunction "99_99") (pintype "unspecified"))
      (node (ref "R1") (pin "1") (pinfunction "1_1") (pintype "unspecified"))
      (node (ref "R18") (pin "1") (pinfunction "1_1") (pintype "unspecified"))
      (node (ref "R2") (pin "1") (pinfunction "1_1") (pintype "unspecified"))
      (node (ref "R3") (pin "1") (pinfunction "1_1") (pintype "unspecified"))
      (node (ref "U1") (pin "11") (pinfunction "GND_11") (pintype "unspecified"))
      (node (ref "U1") (pin "26") (pinfunction "GND_26") (pintype "unspecified"))
      (node (ref "U1") (pin "38") (pinfunction "GND_38") (pintype "unspecified"))
      (node (ref "U1") (pin "43") (pinfunction "GND_43") (pintype "unspecified"))
      (node (ref "U1") (pin "59") (pinfunction "GND_59") (pintype "unspecified"))
      (node (ref "U1") (pin "74") (pinfunction "GND_74") (pintype "unspecified"))
      (node (ref "U1") (pin "86") (pinfunction "GND_86") (pintype "unspecified"))
      (node (ref "U1") (pin "95") (pinfunction "GND_95") (pintype "unspecified"))
      (node (ref "U11") (pin "5") (pinfunction "5_5") (pintype "unspecified"))
      (node (ref "U2") (pin "16") (pinfunction "VSS_16") (pintype "unspecified"))
      (node (ref "U3") (pin "16") (pinfunction "VSS_16") (pintype "unspecified"))
    )
    (net (code "94") (name "VCC") (class "Default")
      (node (ref "C1") (pin "2") (pinfunction "2_2") (pintype "unspecified"))
      (node (ref "C2") (pin "2") (pinfunction "2_2") (pintype "unspecified"))
      (node (ref "C3") (pin "2") (pinfunction "2_2") (pintype "unspecified"))
      (node (ref "C4") (pin "2") (pinfunction "2_2") (pintype "unspecified"))
      (node (ref "C5") (pin "2") (pinfunction "2_2") (pintype "unspecified"))
      (node (ref "C6") (pin "2") (pinfunction "2_2") (pintype "unspecified"))
      (node (ref "C7") (pin "2") (pinfunction "2_2") (pintype "unspecified"))
      (node (ref "C8") (pin "2") (pinfunction "2_2") (pintype "unspecified"))
      (node (ref "CN1") (pin "A2") (pinfunction "A2_A2") (pintype "unspecified"))
      (node (ref "CN1") (pin "A3") (pinfunction "A3_A3") (pintype "unspecified"))
      (node (ref "CN1") (pin "A4") (pinfunction "A4_A4") (pintype "unspecified"))
      (node (ref "CN1") (pin "B2") (pinfunction "B2_B2") (pintype "unspecified"))
      (node (ref "CN1") (pin "B3") (pinfunction "B3_B3") (pintype "unspecified"))
      (node (ref "CN1") (pin "B4") (pinfunction "B4_B4") (pintype "unspecified"))
      (node (ref "CN1") (pin "C2") (pinfunction "C2_C2") (pintype "unspecified"))
      (node (ref "CN1") (pin "C3") (pinfunction "C3_C3") (pintype "unspecified"))
      (node (ref "CN1") (pin "C4") (pinfunction "C4_C4") (pintype "unspecified"))
      (node (ref "CN2") (pin "111") (pinfunction "111_111") (pintype "unspecified"))
      (node (ref "CN2") (pin "112") (pinfunction "112_112") (pintype "unspecified"))
      (node (ref "CN2") (pin "117") (pinfunction "117_117") (pintype "unspecified"))
      (node (ref "CN2") (pin "118") (pinfunction "118_118") (pintype "unspecified"))
      (node (ref "CN2") (pin "123") (pinfunction "123_123") (pintype "unspecified"))
      (node (ref "CN2") (pin "124") (pinfunction "124_124") (pintype "unspecified"))
      (node (ref "CN2") (pin "129") (pinfunction "129_129") (pintype "unspecified"))
      (node (ref "CN2") (pin "130") (pinfunction "130_130") (pintype "unspecified"))
      (node (ref "CN2") (pin "135") (pinfunction "135_135") (pintype "unspecified"))
      (node (ref "CN2") (pin "136") (pinfunction "136_136") (pintype "unspecified"))
      (node (ref "CN2") (pin "141") (pinfunction "141_141") (pintype "unspecified"))
      (node (ref "CN2") (pin "142") (pinfunction "142_142") (pintype "unspecified"))
      (node (ref "CN2") (pin "147") (pinfunction "147_147") (pintype "unspecified"))
      (node (ref "CN2") (pin "148") (pinfunction "148_148") (pintype "unspecified"))
      (node (ref "CN2") (pin "153") (pinfunction "153_153") (pintype "unspecified"))
      (node (ref "CN2") (pin "154") (pinfunction "154_154") (pintype "unspecified"))
      (node (ref "CN2") (pin "159") (pinfunction "159_159") (pintype "unspecified"))
      (node (ref "CN2") (pin "160") (pinfunction "160_160") (pintype "unspecified"))
      (node (ref "CN2") (pin "163") (pinfunction "163_163") (pintype "unspecified"))
      (node (ref "CN3") (pin "111") (pinfunction "111_111") (pintype "unspecified"))
      (node (ref "CN3") (pin "112") (pinfunction "112_112") (pintype "unspecified"))
      (node (ref "CN3") (pin "117") (pinfunction "117_117") (pintype "unspecified"))
      (node (ref "CN3") (pin "118") (pinfunction "118_118") (pintype "unspecified"))
      (node (ref "CN3") (pin "123") (pinfunction "123_123") (pintype "unspecified"))
      (node (ref "CN3") (pin "124") (pinfunction "124_124") (pintype "unspecified"))
      (node (ref "CN3") (pin "129") (pinfunction "129_129") (pintype "unspecified"))
      (node (ref "CN3") (pin "130") (pinfunction "130_130") (pintype "unspecified"))
      (node (ref "CN3") (pin "135") (pinfunction "135_135") (pintype "unspecified"))
      (node (ref "CN3") (pin "136") (pinfunction "136_136") (pintype "unspecified"))
      (node (ref "CN3") (pin "141") (pinfunction "141_141") (pintype "unspecified"))
      (node (ref "CN3") (pin "142") (pinfunction "142_142") (pintype "unspecified"))
      (node (ref "CN3") (pin "147") (pinfunction "147_147") (pintype "unspecified"))
      (node (ref "CN3") (pin "148") (pinfunction "148_148") (pintype "unspecified"))
      (node (ref "CN3") (pin "153") (pinfunction "153_153") (pintype "unspecified"))
      (node (ref "CN3") (pin "154") (pinfunction "154_154") (pintype "unspecified"))
      (node (ref "CN3") (pin "159") (pinfunction "159_159") (pintype "unspecified"))
      (node (ref "CN3") (pin "160") (pinfunction "160_160") (pintype "unspecified"))
      (node (ref "CN3") (pin "163") (pinfunction "163_163") (pintype "unspecified"))
      (node (ref "R10") (pin "1") (pinfunction "1_1") (pintype "unspecified"))
      (node (ref "R11") (pin "1") (pinfunction "1_1") (pintype "unspecified"))
      (node (ref "R12") (pin "1") (pinfunction "1_1") (pintype "unspecified"))
      (node (ref "R13") (pin "1") (pinfunction "1_1") (pintype "unspecified"))
      (node (ref "R14") (pin "1") (pinfunction "1_1") (pintype "unspecified"))
      (node (ref "R15") (pin "1") (pinfunction "1_1") (pintype "unspecified"))
      (node (ref "R16") (pin "1") (pinfunction "1_1") (pintype "unspecified"))
      (node (ref "R17") (pin "1") (pinfunction "1_1") (pintype "unspecified"))
      (node (ref "R19") (pin "2") (pinfunction "2_2") (pintype "unspecified"))
      (node (ref "R20") (pin "2") (pinfunction "2_2") (pintype "unspecified"))
      (node (ref "R21") (pin "2") (pinfunction "2_2") (pintype "unspecified"))
      (node (ref "R22") (pin "2") (pinfunction "2_2") (pintype "unspecified"))
      (node (ref "R4") (pin "1") (pinfunction "1_1") (pintype "unspecified"))
      (node (ref "R5") (pin "1") (pinfunction "1_1") (pintype "unspecified"))
      (node (ref "R6") (pin "1") (pinfunction "1_1") (pintype "unspecified"))
      (node (ref "R7") (pin "1") (pinfunction "1_1") (pintype "unspecified"))
      (node (ref "R8") (pin "1") (pinfunction "1_1") (pintype "unspecified"))
      (node (ref "R9") (pin "1") (pinfunction "1_1") (pintype "unspecified"))
      (node (ref "SW1") (pin "5") (pinfunction "B4_5") (pintype "input"))
      (node (ref "SW1") (pin "6") (pinfunction "B3_6") (pintype "input"))
      (node (ref "SW1") (pin "7") (pinfunction "B2_7") (pintype "input"))
      (node (ref "SW1") (pin "8") (pinfunction "B1_8") (pintype "input"))
      (node (ref "U1") (pin "18") (pinfunction "VCCIO_18") (pintype "unspecified"))
      (node (ref "U1") (pin "3") (pinfunction "VCCIO_3") (pintype "unspecified"))
      (node (ref "U1") (pin "34") (pinfunction "VCCIO_34") (pintype "unspecified"))
      (node (ref "U1") (pin "39") (pinfunction "VCCINT_39") (pintype "unspecified"))
      (node (ref "U1") (pin "51") (pinfunction "VCCIO_51") (pintype "unspecified"))
      (node (ref "U1") (pin "66") (pinfunction "VCCIO_66") (pintype "unspecified"))
      (node (ref "U1") (pin "82") (pinfunction "VCCIO_82") (pintype "unspecified"))
      (node (ref "U1") (pin "91") (pinfunction "VCCINT_91") (pintype "unspecified"))
      (node (ref "U11") (pin "1") (pinfunction "1_1") (pintype "unspecified"))
      (node (ref "U2") (pin "32") (pinfunction "VDD_32") (pintype "unspecified"))
      (node (ref "U3") (pin "32") (pinfunction "VDD_32") (pintype "unspecified"))
    )
    (net (code "95") (name "unconnected-(CN1-PadA5)") (class "Default")
      (node (ref "CN1") (pin "A5") (pinfunction "A5_A5") (pintype "unspecified+no_connect"))
    )
    (net (code "96") (name "unconnected-(CN1-PadA6)") (class "Default")
      (node (ref "CN1") (pin "A6") (pinfunction "A6_A6") (pintype "unspecified+no_connect"))
    )
    (net (code "97") (name "unconnected-(CN1-PadA7)") (class "Default")
      (node (ref "CN1") (pin "A7") (pinfunction "A7_A7") (pintype "unspecified+no_connect"))
    )
    (net (code "98") (name "unconnected-(CN1-PadA16)") (class "Default")
      (node (ref "CN1") (pin "A16") (pinfunction "A16_A16") (pintype "unspecified+no_connect"))
    )
    (net (code "99") (name "unconnected-(CN1-PadA17)") (class "Default")
      (node (ref "CN1") (pin "A17") (pinfunction "A17_A17") (pintype "unspecified+no_connect"))
    )
    (net (code "100") (name "unconnected-(CN1-PadA18)") (class "Default")
      (node (ref "CN1") (pin "A18") (pinfunction "A18_A18") (pintype "unspecified+no_connect"))
    )
    (net (code "101") (name "unconnected-(CN1-PadA19)") (class "Default")
      (node (ref "CN1") (pin "A19") (pinfunction "A19_A19") (pintype "unspecified+no_connect"))
    )
    (net (code "102") (name "unconnected-(CN1-PadA28)") (class "Default")
      (node (ref "CN1") (pin "A28") (pinfunction "A28_A28") (pintype "unspecified+no_connect"))
    )
    (net (code "103") (name "unconnected-(CN1-PadA29)") (class "Default")
      (node (ref "CN1") (pin "A29") (pinfunction "A29_A29") (pintype "unspecified+no_connect"))
    )
    (net (code "104") (name "unconnected-(CN1-PadA30)") (class "Default")
      (node (ref "CN1") (pin "A30") (pinfunction "A30_A30") (pintype "unspecified+no_connect"))
    )
    (net (code "105") (name "unconnected-(CN1-PadB6)") (class "Default")
      (node (ref "CN1") (pin "B6") (pinfunction "B6_B6") (pintype "unspecified+no_connect"))
    )
    (net (code "106") (name "unconnected-(CN1-PadB9)") (class "Default")
      (node (ref "CN1") (pin "B9") (pinfunction "B9_B9") (pintype "unspecified+no_connect"))
    )
    (net (code "107") (name "unconnected-(CN1-PadB16)") (class "Default")
      (node (ref "CN1") (pin "B16") (pinfunction "B16_B16") (pintype "unspecified+no_connect"))
    )
    (net (code "108") (name "unconnected-(CN1-PadB17)") (class "Default")
      (node (ref "CN1") (pin "B17") (pinfunction "B17_B17") (pintype "unspecified+no_connect"))
    )
    (net (code "109") (name "unconnected-(CN1-PadB18)") (class "Default")
      (node (ref "CN1") (pin "B18") (pinfunction "B18_B18") (pintype "unspecified+no_connect"))
    )
    (net (code "110") (name "unconnected-(CN1-PadB19)") (class "Default")
      (node (ref "CN1") (pin "B19") (pinfunction "B19_B19") (pintype "unspecified+no_connect"))
    )
    (net (code "111") (name "unconnected-(CN1-PadB25)") (class "Default")
      (node (ref "CN1") (pin "B25") (pinfunction "B25_B25") (pintype "unspecified+no_connect"))
    )
    (net (code "112") (name "unconnected-(CN1-PadB28)") (class "Default")
      (node (ref "CN1") (pin "B28") (pinfunction "B28_B28") (pintype "unspecified+no_connect"))
    )
    (net (code "113") (name "unconnected-(CN1-PadB29)") (class "Default")
      (node (ref "CN1") (pin "B29") (pinfunction "B29_B29") (pintype "unspecified+no_connect"))
    )
    (net (code "114") (name "unconnected-(CN1-PadC5)") (class "Default")
      (node (ref "CN1") (pin "C5") (pinfunction "C5_C5") (pintype "unspecified+no_connect"))
    )
    (net (code "115") (name "unconnected-(CN1-PadC6)") (class "Default")
      (node (ref "CN1") (pin "C6") (pinfunction "C6_C6") (pintype "unspecified+no_connect"))
    )
    (net (code "116") (name "unconnected-(CN1-PadC15)") (class "Default")
      (node (ref "CN1") (pin "C15") (pinfunction "C15_C15") (pintype "unspecified+no_connect"))
    )
    (net (code "117") (name "unconnected-(CN1-PadC16)") (class "Default")
      (node (ref "CN1") (pin "C16") (pinfunction "C16_C16") (pintype "unspecified+no_connect"))
    )
    (net (code "118") (name "unconnected-(CN1-PadC17)") (class "Default")
      (node (ref "CN1") (pin "C17") (pinfunction "C17_C17") (pintype "unspecified+no_connect"))
    )
    (net (code "119") (name "unconnected-(CN1-PadC18)") (class "Default")
      (node (ref "CN1") (pin "C18") (pinfunction "C18_C18") (pintype "unspecified+no_connect"))
    )
    (net (code "120") (name "unconnected-(CN1-PadC27)") (class "Default")
      (node (ref "CN1") (pin "C27") (pinfunction "C27_C27") (pintype "unspecified+no_connect"))
    )
    (net (code "121") (name "unconnected-(CN1-PadC28)") (class "Default")
      (node (ref "CN1") (pin "C28") (pinfunction "C28_C28") (pintype "unspecified+no_connect"))
    )
    (net (code "122") (name "unconnected-(CN1-PadC29)") (class "Default")
      (node (ref "CN1") (pin "C29") (pinfunction "C29_C29") (pintype "unspecified+no_connect"))
    )
    (net (code "123") (name "unconnected-(CN2-Pad3)") (class "Default")
      (node (ref "CN2") (pin "3") (pinfunction "3_3") (pintype "unspecified+no_connect"))
    )
    (net (code "124") (name "unconnected-(CN2-Pad4)") (class "Default")
      (node (ref "CN2") (pin "4") (pinfunction "4_4") (pintype "unspecified+no_connect"))
    )
    (net (code "125") (name "unconnected-(CN2-Pad7)") (class "Default")
      (node (ref "CN2") (pin "7") (pinfunction "7_7") (pintype "unspecified+no_connect"))
    )
    (net (code "126") (name "unconnected-(CN2-Pad28)") (class "Default")
      (node (ref "CN2") (pin "28") (pinfunction "28_28") (pintype "unspecified+no_connect"))
    )
    (net (code "127") (name "unconnected-(CN2-Pad29)") (class "Default")
      (node (ref "CN2") (pin "29") (pinfunction "29_29") (pintype "unspecified+no_connect"))
    )
    (net (code "128") (name "unconnected-(CN2-Pad32)") (class "Default")
      (node (ref "CN2") (pin "32") (pinfunction "32_32") (pintype "unspecified+no_connect"))
    )
    (net (code "129") (name "unconnected-(CN2-Pad33)") (class "Default")
      (node (ref "CN2") (pin "33") (pinfunction "33_33") (pintype "unspecified+no_connect"))
    )
    (net (code "130") (name "unconnected-(CN2-Pad34)") (class "Default")
      (node (ref "CN2") (pin "34") (pinfunction "34_34") (pintype "unspecified+no_connect"))
    )
    (net (code "131") (name "unconnected-(CN2-Pad37)") (class "Default")
      (node (ref "CN2") (pin "37") (pinfunction "37_37") (pintype "unspecified+no_connect"))
    )
    (net (code "132") (name "unconnected-(CN2-Pad38)") (class "Default")
      (node (ref "CN2") (pin "38") (pinfunction "38_38") (pintype "unspecified+no_connect"))
    )
    (net (code "133") (name "unconnected-(CN2-Pad41)") (class "Default")
      (node (ref "CN2") (pin "41") (pinfunction "41_41") (pintype "unspecified+no_connect"))
    )
    (net (code "134") (name "unconnected-(CN2-Pad42)") (class "Default")
      (node (ref "CN2") (pin "42") (pinfunction "42_42") (pintype "unspecified+no_connect"))
    )
    (net (code "135") (name "unconnected-(CN2-Pad45)") (class "Default")
      (node (ref "CN2") (pin "45") (pinfunction "45_45") (pintype "unspecified+no_connect"))
    )
    (net (code "136") (name "unconnected-(CN2-Pad63)") (class "Default")
      (node (ref "CN2") (pin "63") (pinfunction "63_63") (pintype "unspecified+no_connect"))
    )
    (net (code "137") (name "unconnected-(CN2-Pad74)") (class "Default")
      (node (ref "CN2") (pin "74") (pinfunction "74_74") (pintype "unspecified+no_connect"))
    )
    (net (code "138") (name "unconnected-(CN2-Pad76)") (class "Default")
      (node (ref "CN2") (pin "76") (pinfunction "76_76") (pintype "unspecified+no_connect"))
    )
    (net (code "139") (name "unconnected-(CN2-Pad79)") (class "Default")
      (node (ref "CN2") (pin "79") (pinfunction "79_79") (pintype "unspecified+no_connect"))
    )
    (net (code "140") (name "unconnected-(CN2-Pad84)") (class "Default")
      (node (ref "CN2") (pin "84") (pinfunction "84_84") (pintype "unspecified+no_connect"))
    )
    (net (code "141") (name "unconnected-(CN2-Pad87)") (class "Default")
      (node (ref "CN2") (pin "87") (pinfunction "87_87") (pintype "unspecified+no_connect"))
    )
    (net (code "142") (name "unconnected-(CN2-Pad97)") (class "Default")
      (node (ref "CN2") (pin "97") (pinfunction "97_97") (pintype "unspecified+no_connect"))
    )
    (net (code "143") (name "unconnected-(CN2-Pad100)") (class "Default")
      (node (ref "CN2") (pin "100") (pinfunction "100_100") (pintype "unspecified+no_connect"))
    )
    (net (code "144") (name "unconnected-(CN2-Pad101)") (class "Default")
      (node (ref "CN2") (pin "101") (pinfunction "101_101") (pintype "unspecified+no_connect"))
    )
    (net (code "145") (name "unconnected-(CN2-Pad104)") (class "Default")
      (node (ref "CN2") (pin "104") (pinfunction "104_104") (pintype "unspecified+no_connect"))
    )
    (net (code "146") (name "unconnected-(CN2-Pad113)") (class "Default")
      (node (ref "CN2") (pin "113") (pinfunction "113_113") (pintype "unspecified+no_connect"))
    )
    (net (code "147") (name "unconnected-(CN2-Pad114)") (class "Default")
      (node (ref "CN2") (pin "114") (pinfunction "114_114") (pintype "unspecified+no_connect"))
    )
    (net (code "148") (name "unconnected-(CN2-Pad115)") (class "Default")
      (node (ref "CN2") (pin "115") (pinfunction "115_115") (pintype "unspecified+no_connect"))
    )
    (net (code "149") (name "unconnected-(CN2-Pad116)") (class "Default")
      (node (ref "CN2") (pin "116") (pinfunction "116_116") (pintype "unspecified+no_connect"))
    )
    (net (code "150") (name "unconnected-(CN2-Pad119)") (class "Default")
      (node (ref "CN2") (pin "119") (pinfunction "119_119") (pintype "unspecified+no_connect"))
    )
    (net (code "151") (name "unconnected-(CN2-Pad120)") (class "Default")
      (node (ref "CN2") (pin "120") (pinfunction "120_120") (pintype "unspecified+no_connect"))
    )
    (net (code "152") (name "unconnected-(CN2-Pad122)") (class "Default")
      (node (ref "CN2") (pin "122") (pinfunction "122_122") (pintype "unspecified+no_connect"))
    )
    (net (code "153") (name "unconnected-(CN2-Pad125)") (class "Default")
      (node (ref "CN2") (pin "125") (pinfunction "125_125") (pintype "unspecified+no_connect"))
    )
    (net (code "154") (name "unconnected-(CN2-Pad126)") (class "Default")
      (node (ref "CN2") (pin "126") (pinfunction "126_126") (pintype "unspecified+no_connect"))
    )
    (net (code "155") (name "unconnected-(CN2-Pad131)") (class "Default")
      (node (ref "CN2") (pin "131") (pinfunction "131_131") (pintype "unspecified+no_connect"))
    )
    (net (code "156") (name "unconnected-(CN2-Pad132)") (class "Default")
      (node (ref "CN2") (pin "132") (pinfunction "132_132") (pintype "unspecified+no_connect"))
    )
    (net (code "157") (name "unconnected-(CN2-Pad133)") (class "Default")
      (node (ref "CN2") (pin "133") (pinfunction "133_133") (pintype "unspecified+no_connect"))
    )
    (net (code "158") (name "unconnected-(CN2-Pad134)") (class "Default")
      (node (ref "CN2") (pin "134") (pinfunction "134_134") (pintype "unspecified+no_connect"))
    )
    (net (code "159") (name "unconnected-(CN2-Pad137)") (class "Default")
      (node (ref "CN2") (pin "137") (pinfunction "137_137") (pintype "unspecified+no_connect"))
    )
    (net (code "160") (name "unconnected-(CN2-Pad138)") (class "Default")
      (node (ref "CN2") (pin "138") (pinfunction "138_138") (pintype "unspecified+no_connect"))
    )
    (net (code "161") (name "unconnected-(CN2-Pad139)") (class "Default")
      (node (ref "CN2") (pin "139") (pinfunction "139_139") (pintype "unspecified+no_connect"))
    )
    (net (code "162") (name "unconnected-(CN2-Pad140)") (class "Default")
      (node (ref "CN2") (pin "140") (pinfunction "140_140") (pintype "unspecified+no_connect"))
    )
    (net (code "163") (name "unconnected-(CN2-Pad143)") (class "Default")
      (node (ref "CN2") (pin "143") (pinfunction "143_143") (pintype "unspecified+no_connect"))
    )
    (net (code "164") (name "unconnected-(CN2-Pad144)") (class "Default")
      (node (ref "CN2") (pin "144") (pinfunction "144_144") (pintype "unspecified+no_connect"))
    )
    (net (code "165") (name "unconnected-(CN2-Pad145)") (class "Default")
      (node (ref "CN2") (pin "145") (pinfunction "145_145") (pintype "unspecified+no_connect"))
    )
    (net (code "166") (name "unconnected-(CN2-Pad146)") (class "Default")
      (node (ref "CN2") (pin "146") (pinfunction "146_146") (pintype "unspecified+no_connect"))
    )
    (net (code "167") (name "unconnected-(CN2-Pad149)") (class "Default")
      (node (ref "CN2") (pin "149") (pinfunction "149_149") (pintype "unspecified+no_connect"))
    )
    (net (code "168") (name "unconnected-(CN2-Pad150)") (class "Default")
      (node (ref "CN2") (pin "150") (pinfunction "150_150") (pintype "unspecified+no_connect"))
    )
    (net (code "169") (name "unconnected-(CN2-Pad151)") (class "Default")
      (node (ref "CN2") (pin "151") (pinfunction "151_151") (pintype "unspecified+no_connect"))
    )
    (net (code "170") (name "unconnected-(CN2-Pad152)") (class "Default")
      (node (ref "CN2") (pin "152") (pinfunction "152_152") (pintype "unspecified+no_connect"))
    )
    (net (code "171") (name "unconnected-(CN2-Pad155)") (class "Default")
      (node (ref "CN2") (pin "155") (pinfunction "155_155") (pintype "unspecified+no_connect"))
    )
    (net (code "172") (name "unconnected-(CN2-Pad156)") (class "Default")
      (node (ref "CN2") (pin "156") (pinfunction "156_156") (pintype "unspecified+no_connect"))
    )
    (net (code "173") (name "unconnected-(CN2-Pad161)") (class "Default")
      (node (ref "CN2") (pin "161") (pinfunction "161_161") (pintype "unspecified+no_connect"))
    )
    (net (code "174") (name "unconnected-(CN2-Pad162)") (class "Default")
      (node (ref "CN2") (pin "162") (pinfunction "162_162") (pintype "unspecified+no_connect"))
    )
    (net (code "175") (name "unconnected-(CN2-Pad177)") (class "Default")
      (node (ref "CN2") (pin "177") (pinfunction "177_177") (pintype "unspecified+no_connect"))
    )
    (net (code "176") (name "unconnected-(CN2-Pad178)") (class "Default")
      (node (ref "CN2") (pin "178") (pinfunction "178_178") (pintype "unspecified+no_connect"))
    )
    (net (code "177") (name "unconnected-(CN2-Pad179)") (class "Default")
      (node (ref "CN2") (pin "179") (pinfunction "179_179") (pintype "unspecified+no_connect"))
    )
    (net (code "178") (name "unconnected-(CN2-Pad182)") (class "Default")
      (node (ref "CN2") (pin "182") (pinfunction "182_182") (pintype "unspecified+no_connect"))
    )
    (net (code "179") (name "unconnected-(CN2-Pad183)") (class "Default")
      (node (ref "CN2") (pin "183") (pinfunction "183_183") (pintype "unspecified+no_connect"))
    )
    (net (code "180") (name "unconnected-(CN2-Pad186)") (class "Default")
      (node (ref "CN2") (pin "186") (pinfunction "186_186") (pintype "unspecified+no_connect"))
    )
    (net (code "181") (name "unconnected-(CN2-Pad187)") (class "Default")
      (node (ref "CN2") (pin "187") (pinfunction "187_187") (pintype "unspecified+no_connect"))
    )
    (net (code "182") (name "unconnected-(CN2-Pad190)") (class "Default")
      (node (ref "CN2") (pin "190") (pinfunction "190_190") (pintype "unspecified+no_connect"))
    )
    (net (code "183") (name "unconnected-(CN2-Pad191)") (class "Default")
      (node (ref "CN2") (pin "191") (pinfunction "191_191") (pintype "unspecified+no_connect"))
    )
    (net (code "184") (name "unconnected-(CN2-Pad194)") (class "Default")
      (node (ref "CN2") (pin "194") (pinfunction "194_194") (pintype "unspecified+no_connect"))
    )
    (net (code "185") (name "unconnected-(CN2-Pad211)") (class "Default")
      (node (ref "CN2") (pin "211") (pinfunction "211_211") (pintype "unspecified+no_connect"))
    )
    (net (code "186") (name "unconnected-(CN2-Pad212)") (class "Default")
      (node (ref "CN2") (pin "212") (pinfunction "212_212") (pintype "unspecified+no_connect"))
    )
    (net (code "187") (name "unconnected-(CN2-Pad215)") (class "Default")
      (node (ref "CN2") (pin "215") (pinfunction "215_215") (pintype "unspecified+no_connect"))
    )
    (net (code "188") (name "unconnected-(CN2-Pad216)") (class "Default")
      (node (ref "CN2") (pin "216") (pinfunction "216_216") (pintype "unspecified+no_connect"))
    )
    (net (code "189") (name "unconnected-(CN2-Pad219)") (class "Default")
      (node (ref "CN2") (pin "219") (pinfunction "219_219") (pintype "unspecified+no_connect"))
    )
    (net (code "190") (name "unconnected-(CN2-Pad220)") (class "Default")
      (node (ref "CN2") (pin "220") (pinfunction "220_220") (pintype "unspecified+no_connect"))
    )
    (net (code "191") (name "unconnected-(CN2-Pad221)") (class "Default")
      (node (ref "CN2") (pin "221") (pinfunction "221_221") (pintype "unspecified+no_connect"))
    )
    (net (code "192") (name "unconnected-(CN2-Pad224)") (class "Default")
      (node (ref "CN2") (pin "224") (pinfunction "224_224") (pintype "unspecified+no_connect"))
    )
    (net (code "193") (name "unconnected-(CN2-Pad225)") (class "Default")
      (node (ref "CN2") (pin "225") (pinfunction "225_225") (pintype "unspecified+no_connect"))
    )
    (net (code "194") (name "unconnected-(CN2-Pad228)") (class "Default")
      (node (ref "CN2") (pin "228") (pinfunction "228_228") (pintype "unspecified+no_connect"))
    )
    (net (code "195") (name "unconnected-(CN2-Pad229)") (class "Default")
      (node (ref "CN2") (pin "229") (pinfunction "229_229") (pintype "unspecified+no_connect"))
    )
    (net (code "196") (name "unconnected-(CN2-Pad232)") (class "Default")
      (node (ref "CN2") (pin "232") (pinfunction "232_232") (pintype "unspecified+no_connect"))
    )
    (net (code "197") (name "unconnected-(CN2-Pad249)") (class "Default")
      (node (ref "CN2") (pin "249") (pinfunction "249_249") (pintype "unspecified+no_connect"))
    )
    (net (code "198") (name "unconnected-(CN2-Pad250)") (class "Default")
      (node (ref "CN2") (pin "250") (pinfunction "250_250") (pintype "unspecified+no_connect"))
    )
    (net (code "199") (name "unconnected-(CN2-Pad253)") (class "Default")
      (node (ref "CN2") (pin "253") (pinfunction "253_253") (pintype "unspecified+no_connect"))
    )
    (net (code "200") (name "unconnected-(CN2-Pad254)") (class "Default")
      (node (ref "CN2") (pin "254") (pinfunction "254_254") (pintype "unspecified+no_connect"))
    )
    (net (code "201") (name "unconnected-(CN2-Pad255)") (class "Default")
      (node (ref "CN2") (pin "255") (pinfunction "255_255") (pintype "unspecified+no_connect"))
    )
    (net (code "202") (name "unconnected-(CN2-Pad256)") (class "Default")
      (node (ref "CN2") (pin "256") (pinfunction "256_256") (pintype "unspecified+no_connect"))
    )
    (net (code "203") (name "unconnected-(CN2-Pad257)") (class "Default")
      (node (ref "CN2") (pin "257") (pinfunction "257_257") (pintype "unspecified+no_connect"))
    )
    (net (code "204") (name "unconnected-(CN2-Pad258)") (class "Default")
      (node (ref "CN2") (pin "258") (pinfunction "258_258") (pintype "unspecified+no_connect"))
    )
    (net (code "205") (name "unconnected-(CN2-Pad259)") (class "Default")
      (node (ref "CN2") (pin "259") (pinfunction "259_259") (pintype "unspecified+no_connect"))
    )
    (net (code "206") (name "unconnected-(CN2-Pad260)") (class "Default")
      (node (ref "CN2") (pin "260") (pinfunction "260_260") (pintype "unspecified+no_connect"))
    )
    (net (code "207") (name "unconnected-(CN2-Pad261)") (class "Default")
      (node (ref "CN2") (pin "261") (pinfunction "261_261") (pintype "unspecified+no_connect"))
    )
    (net (code "208") (name "unconnected-(CN2-Pad262)") (class "Default")
      (node (ref "CN2") (pin "262") (pinfunction "262_262") (pintype "unspecified+no_connect"))
    )
    (net (code "209") (name "unconnected-(CN3-Pad3)") (class "Default")
      (node (ref "CN3") (pin "3") (pinfunction "3_3") (pintype "unspecified+no_connect"))
    )
    (net (code "210") (name "unconnected-(CN3-Pad4)") (class "Default")
      (node (ref "CN3") (pin "4") (pinfunction "4_4") (pintype "unspecified+no_connect"))
    )
    (net (code "211") (name "unconnected-(CN3-Pad7)") (class "Default")
      (node (ref "CN3") (pin "7") (pinfunction "7_7") (pintype "unspecified+no_connect"))
    )
    (net (code "212") (name "unconnected-(CN3-Pad28)") (class "Default")
      (node (ref "CN3") (pin "28") (pinfunction "28_28") (pintype "unspecified+no_connect"))
    )
    (net (code "213") (name "unconnected-(CN3-Pad29)") (class "Default")
      (node (ref "CN3") (pin "29") (pinfunction "29_29") (pintype "unspecified+no_connect"))
    )
    (net (code "214") (name "unconnected-(CN3-Pad32)") (class "Default")
      (node (ref "CN3") (pin "32") (pinfunction "32_32") (pintype "unspecified+no_connect"))
    )
    (net (code "215") (name "unconnected-(CN3-Pad33)") (class "Default")
      (node (ref "CN3") (pin "33") (pinfunction "33_33") (pintype "unspecified+no_connect"))
    )
    (net (code "216") (name "unconnected-(CN3-Pad34)") (class "Default")
      (node (ref "CN3") (pin "34") (pinfunction "34_34") (pintype "unspecified+no_connect"))
    )
    (net (code "217") (name "unconnected-(CN3-Pad37)") (class "Default")
      (node (ref "CN3") (pin "37") (pinfunction "37_37") (pintype "unspecified+no_connect"))
    )
    (net (code "218") (name "unconnected-(CN3-Pad38)") (class "Default")
      (node (ref "CN3") (pin "38") (pinfunction "38_38") (pintype "unspecified+no_connect"))
    )
    (net (code "219") (name "unconnected-(CN3-Pad41)") (class "Default")
      (node (ref "CN3") (pin "41") (pinfunction "41_41") (pintype "unspecified+no_connect"))
    )
    (net (code "220") (name "unconnected-(CN3-Pad42)") (class "Default")
      (node (ref "CN3") (pin "42") (pinfunction "42_42") (pintype "unspecified+no_connect"))
    )
    (net (code "221") (name "unconnected-(CN3-Pad45)") (class "Default")
      (node (ref "CN3") (pin "45") (pinfunction "45_45") (pintype "unspecified+no_connect"))
    )
    (net (code "222") (name "unconnected-(CN3-Pad63)") (class "Default")
      (node (ref "CN3") (pin "63") (pinfunction "63_63") (pintype "unspecified+no_connect"))
    )
    (net (code "223") (name "unconnected-(CN3-Pad74)") (class "Default")
      (node (ref "CN3") (pin "74") (pinfunction "74_74") (pintype "unspecified+no_connect"))
    )
    (net (code "224") (name "unconnected-(CN3-Pad76)") (class "Default")
      (node (ref "CN3") (pin "76") (pinfunction "76_76") (pintype "unspecified+no_connect"))
    )
    (net (code "225") (name "unconnected-(CN3-Pad79)") (class "Default")
      (node (ref "CN3") (pin "79") (pinfunction "79_79") (pintype "unspecified+no_connect"))
    )
    (net (code "226") (name "unconnected-(CN3-Pad84)") (class "Default")
      (node (ref "CN3") (pin "84") (pinfunction "84_84") (pintype "unspecified+no_connect"))
    )
    (net (code "227") (name "unconnected-(CN3-Pad87)") (class "Default")
      (node (ref "CN3") (pin "87") (pinfunction "87_87") (pintype "unspecified+no_connect"))
    )
    (net (code "228") (name "unconnected-(CN3-Pad97)") (class "Default")
      (node (ref "CN3") (pin "97") (pinfunction "97_97") (pintype "unspecified+no_connect"))
    )
    (net (code "229") (name "unconnected-(CN3-Pad100)") (class "Default")
      (node (ref "CN3") (pin "100") (pinfunction "100_100") (pintype "unspecified+no_connect"))
    )
    (net (code "230") (name "unconnected-(CN3-Pad101)") (class "Default")
      (node (ref "CN3") (pin "101") (pinfunction "101_101") (pintype "unspecified+no_connect"))
    )
    (net (code "231") (name "unconnected-(CN3-Pad104)") (class "Default")
      (node (ref "CN3") (pin "104") (pinfunction "104_104") (pintype "unspecified+no_connect"))
    )
    (net (code "232") (name "unconnected-(CN3-Pad113)") (class "Default")
      (node (ref "CN3") (pin "113") (pinfunction "113_113") (pintype "unspecified+no_connect"))
    )
    (net (code "233") (name "unconnected-(CN3-Pad114)") (class "Default")
      (node (ref "CN3") (pin "114") (pinfunction "114_114") (pintype "unspecified+no_connect"))
    )
    (net (code "234") (name "unconnected-(CN3-Pad115)") (class "Default")
      (node (ref "CN3") (pin "115") (pinfunction "115_115") (pintype "unspecified+no_connect"))
    )
    (net (code "235") (name "unconnected-(CN3-Pad116)") (class "Default")
      (node (ref "CN3") (pin "116") (pinfunction "116_116") (pintype "unspecified+no_connect"))
    )
    (net (code "236") (name "unconnected-(CN3-Pad119)") (class "Default")
      (node (ref "CN3") (pin "119") (pinfunction "119_119") (pintype "unspecified+no_connect"))
    )
    (net (code "237") (name "unconnected-(CN3-Pad120)") (class "Default")
      (node (ref "CN3") (pin "120") (pinfunction "120_120") (pintype "unspecified+no_connect"))
    )
    (net (code "238") (name "unconnected-(CN3-Pad122)") (class "Default")
      (node (ref "CN3") (pin "122") (pinfunction "122_122") (pintype "unspecified+no_connect"))
    )
    (net (code "239") (name "unconnected-(CN3-Pad125)") (class "Default")
      (node (ref "CN3") (pin "125") (pinfunction "125_125") (pintype "unspecified+no_connect"))
    )
    (net (code "240") (name "unconnected-(CN3-Pad126)") (class "Default")
      (node (ref "CN3") (pin "126") (pinfunction "126_126") (pintype "unspecified+no_connect"))
    )
    (net (code "241") (name "unconnected-(CN3-Pad131)") (class "Default")
      (node (ref "CN3") (pin "131") (pinfunction "131_131") (pintype "unspecified+no_connect"))
    )
    (net (code "242") (name "unconnected-(CN3-Pad132)") (class "Default")
      (node (ref "CN3") (pin "132") (pinfunction "132_132") (pintype "unspecified+no_connect"))
    )
    (net (code "243") (name "unconnected-(CN3-Pad133)") (class "Default")
      (node (ref "CN3") (pin "133") (pinfunction "133_133") (pintype "unspecified+no_connect"))
    )
    (net (code "244") (name "unconnected-(CN3-Pad134)") (class "Default")
      (node (ref "CN3") (pin "134") (pinfunction "134_134") (pintype "unspecified+no_connect"))
    )
    (net (code "245") (name "unconnected-(CN3-Pad137)") (class "Default")
      (node (ref "CN3") (pin "137") (pinfunction "137_137") (pintype "unspecified+no_connect"))
    )
    (net (code "246") (name "unconnected-(CN3-Pad138)") (class "Default")
      (node (ref "CN3") (pin "138") (pinfunction "138_138") (pintype "unspecified+no_connect"))
    )
    (net (code "247") (name "unconnected-(CN3-Pad139)") (class "Default")
      (node (ref "CN3") (pin "139") (pinfunction "139_139") (pintype "unspecified+no_connect"))
    )
    (net (code "248") (name "unconnected-(CN3-Pad140)") (class "Default")
      (node (ref "CN3") (pin "140") (pinfunction "140_140") (pintype "unspecified+no_connect"))
    )
    (net (code "249") (name "unconnected-(CN3-Pad143)") (class "Default")
      (node (ref "CN3") (pin "143") (pinfunction "143_143") (pintype "unspecified+no_connect"))
    )
    (net (code "250") (name "unconnected-(CN3-Pad144)") (class "Default")
      (node (ref "CN3") (pin "144") (pinfunction "144_144") (pintype "unspecified+no_connect"))
    )
    (net (code "251") (name "unconnected-(CN3-Pad145)") (class "Default")
      (node (ref "CN3") (pin "145") (pinfunction "145_145") (pintype "unspecified+no_connect"))
    )
    (net (code "252") (name "unconnected-(CN3-Pad146)") (class "Default")
      (node (ref "CN3") (pin "146") (pinfunction "146_146") (pintype "unspecified+no_connect"))
    )
    (net (code "253") (name "unconnected-(CN3-Pad149)") (class "Default")
      (node (ref "CN3") (pin "149") (pinfunction "149_149") (pintype "unspecified+no_connect"))
    )
    (net (code "254") (name "unconnected-(CN3-Pad150)") (class "Default")
      (node (ref "CN3") (pin "150") (pinfunction "150_150") (pintype "unspecified+no_connect"))
    )
    (net (code "255") (name "unconnected-(CN3-Pad151)") (class "Default")
      (node (ref "CN3") (pin "151") (pinfunction "151_151") (pintype "unspecified+no_connect"))
    )
    (net (code "256") (name "unconnected-(CN3-Pad152)") (class "Default")
      (node (ref "CN3") (pin "152") (pinfunction "152_152") (pintype "unspecified+no_connect"))
    )
    (net (code "257") (name "unconnected-(CN3-Pad155)") (class "Default")
      (node (ref "CN3") (pin "155") (pinfunction "155_155") (pintype "unspecified+no_connect"))
    )
    (net (code "258") (name "unconnected-(CN3-Pad156)") (class "Default")
      (node (ref "CN3") (pin "156") (pinfunction "156_156") (pintype "unspecified+no_connect"))
    )
    (net (code "259") (name "unconnected-(CN3-Pad161)") (class "Default")
      (node (ref "CN3") (pin "161") (pinfunction "161_161") (pintype "unspecified+no_connect"))
    )
    (net (code "260") (name "unconnected-(CN3-Pad162)") (class "Default")
      (node (ref "CN3") (pin "162") (pinfunction "162_162") (pintype "unspecified+no_connect"))
    )
    (net (code "261") (name "unconnected-(CN3-Pad177)") (class "Default")
      (node (ref "CN3") (pin "177") (pinfunction "177_177") (pintype "unspecified+no_connect"))
    )
    (net (code "262") (name "unconnected-(CN3-Pad178)") (class "Default")
      (node (ref "CN3") (pin "178") (pinfunction "178_178") (pintype "unspecified+no_connect"))
    )
    (net (code "263") (name "unconnected-(CN3-Pad179)") (class "Default")
      (node (ref "CN3") (pin "179") (pinfunction "179_179") (pintype "unspecified+no_connect"))
    )
    (net (code "264") (name "unconnected-(CN3-Pad182)") (class "Default")
      (node (ref "CN3") (pin "182") (pinfunction "182_182") (pintype "unspecified+no_connect"))
    )
    (net (code "265") (name "unconnected-(CN3-Pad183)") (class "Default")
      (node (ref "CN3") (pin "183") (pinfunction "183_183") (pintype "unspecified+no_connect"))
    )
    (net (code "266") (name "unconnected-(CN3-Pad186)") (class "Default")
      (node (ref "CN3") (pin "186") (pinfunction "186_186") (pintype "unspecified+no_connect"))
    )
    (net (code "267") (name "unconnected-(CN3-Pad187)") (class "Default")
      (node (ref "CN3") (pin "187") (pinfunction "187_187") (pintype "unspecified+no_connect"))
    )
    (net (code "268") (name "unconnected-(CN3-Pad190)") (class "Default")
      (node (ref "CN3") (pin "190") (pinfunction "190_190") (pintype "unspecified+no_connect"))
    )
    (net (code "269") (name "unconnected-(CN3-Pad191)") (class "Default")
      (node (ref "CN3") (pin "191") (pinfunction "191_191") (pintype "unspecified+no_connect"))
    )
    (net (code "270") (name "unconnected-(CN3-Pad194)") (class "Default")
      (node (ref "CN3") (pin "194") (pinfunction "194_194") (pintype "unspecified+no_connect"))
    )
    (net (code "271") (name "unconnected-(CN3-Pad211)") (class "Default")
      (node (ref "CN3") (pin "211") (pinfunction "211_211") (pintype "unspecified+no_connect"))
    )
    (net (code "272") (name "unconnected-(CN3-Pad212)") (class "Default")
      (node (ref "CN3") (pin "212") (pinfunction "212_212") (pintype "unspecified+no_connect"))
    )
    (net (code "273") (name "unconnected-(CN3-Pad215)") (class "Default")
      (node (ref "CN3") (pin "215") (pinfunction "215_215") (pintype "unspecified+no_connect"))
    )
    (net (code "274") (name "unconnected-(CN3-Pad216)") (class "Default")
      (node (ref "CN3") (pin "216") (pinfunction "216_216") (pintype "unspecified+no_connect"))
    )
    (net (code "275") (name "unconnected-(CN3-Pad219)") (class "Default")
      (node (ref "CN3") (pin "219") (pinfunction "219_219") (pintype "unspecified+no_connect"))
    )
    (net (code "276") (name "unconnected-(CN3-Pad220)") (class "Default")
      (node (ref "CN3") (pin "220") (pinfunction "220_220") (pintype "unspecified+no_connect"))
    )
    (net (code "277") (name "unconnected-(CN3-Pad221)") (class "Default")
      (node (ref "CN3") (pin "221") (pinfunction "221_221") (pintype "unspecified+no_connect"))
    )
    (net (code "278") (name "unconnected-(CN3-Pad224)") (class "Default")
      (node (ref "CN3") (pin "224") (pinfunction "224_224") (pintype "unspecified+no_connect"))
    )
    (net (code "279") (name "unconnected-(CN3-Pad225)") (class "Default")
      (node (ref "CN3") (pin "225") (pinfunction "225_225") (pintype "unspecified+no_connect"))
    )
    (net (code "280") (name "unconnected-(CN3-Pad228)") (class "Default")
      (node (ref "CN3") (pin "228") (pinfunction "228_228") (pintype "unspecified+no_connect"))
    )
    (net (code "281") (name "unconnected-(CN3-Pad229)") (class "Default")
      (node (ref "CN3") (pin "229") (pinfunction "229_229") (pintype "unspecified+no_connect"))
    )
    (net (code "282") (name "unconnected-(CN3-Pad232)") (class "Default")
      (node (ref "CN3") (pin "232") (pinfunction "232_232") (pintype "unspecified+no_connect"))
    )
    (net (code "283") (name "unconnected-(CN3-Pad249)") (class "Default")
      (node (ref "CN3") (pin "249") (pinfunction "249_249") (pintype "unspecified+no_connect"))
    )
    (net (code "284") (name "unconnected-(CN3-Pad250)") (class "Default")
      (node (ref "CN3") (pin "250") (pinfunction "250_250") (pintype "unspecified+no_connect"))
    )
    (net (code "285") (name "unconnected-(CN3-Pad253)") (class "Default")
      (node (ref "CN3") (pin "253") (pinfunction "253_253") (pintype "unspecified+no_connect"))
    )
    (net (code "286") (name "unconnected-(CN3-Pad254)") (class "Default")
      (node (ref "CN3") (pin "254") (pinfunction "254_254") (pintype "unspecified+no_connect"))
    )
    (net (code "287") (name "unconnected-(CN3-Pad255)") (class "Default")
      (node (ref "CN3") (pin "255") (pinfunction "255_255") (pintype "unspecified+no_connect"))
    )
    (net (code "288") (name "unconnected-(CN3-Pad256)") (class "Default")
      (node (ref "CN3") (pin "256") (pinfunction "256_256") (pintype "unspecified+no_connect"))
    )
    (net (code "289") (name "unconnected-(CN3-Pad257)") (class "Default")
      (node (ref "CN3") (pin "257") (pinfunction "257_257") (pintype "unspecified+no_connect"))
    )
    (net (code "290") (name "unconnected-(CN3-Pad258)") (class "Default")
      (node (ref "CN3") (pin "258") (pinfunction "258_258") (pintype "unspecified+no_connect"))
    )
    (net (code "291") (name "unconnected-(CN3-Pad259)") (class "Default")
      (node (ref "CN3") (pin "259") (pinfunction "259_259") (pintype "unspecified+no_connect"))
    )
    (net (code "292") (name "unconnected-(CN3-Pad260)") (class "Default")
      (node (ref "CN3") (pin "260") (pinfunction "260_260") (pintype "unspecified+no_connect"))
    )
    (net (code "293") (name "unconnected-(CN3-Pad261)") (class "Default")
      (node (ref "CN3") (pin "261") (pinfunction "261_261") (pintype "unspecified+no_connect"))
    )
    (net (code "294") (name "unconnected-(CN3-Pad262)") (class "Default")
      (node (ref "CN3") (pin "262") (pinfunction "262_262") (pintype "unspecified+no_connect"))
    )
    (net (code "295") (name "unconnected-(U1-INPUT{slash}OE1-Pad88)") (class "Default")
      (node (ref "U1") (pin "88") (pinfunction "INPUT/OE1_88") (pintype "unspecified+no_connect"))
    )
    (net (code "296") (name "unconnected-(U1-INPUT{slash}OE2{slash}GCLK2-Pad90)") (class "Default")
      (node (ref "U1") (pin "90") (pinfunction "INPUT/OE2/GCLK2_90") (pintype "unspecified+no_connect"))
    )
    (net (code "297") (name "unconnected-(U1-I{slash}O-Pad61)") (class "Default")
      (node (ref "U1") (pin "61") (pinfunction "I/O_61") (pintype "unspecified"))
    )
    (net (code "298") (name "unconnected-(U1-I{slash}O-Pad84)") (class "Default")
      (node (ref "U1") (pin "84") (pinfunction "I/O_84") (pintype "unspecified"))
    )
    (net (code "299") (name "unconnected-(U1-I{slash}O-Pad93)") (class "Default")
      (node (ref "U1") (pin "93") (pinfunction "I/O_93") (pintype "unspecified"))
    )
    (net (code "300") (name "unconnected-(U1-I{slash}O-Pad94)") (class "Default")
      (node (ref "U1") (pin "94") (pinfunction "I/O_94") (pintype "unspecified"))
    )
    (net (code "301") (name "unconnected-(U1-I{slash}O{slash}GCLK3-Pad85)") (class "Default")
      (node (ref "U1") (pin "85") (pinfunction "I/O/GCLK3_85") (pintype "unspecified"))
    )
    (net (code "302") (name "unconnected-(U1-NC-Pad1)") (class "Default")
      (node (ref "U1") (pin "1") (pinfunction "NC_1") (pintype "unspecified+no_connect"))
    )
    (net (code "303") (name "unconnected-(U1-NC-Pad2)") (class "Default")
      (node (ref "U1") (pin "2") (pinfunction "NC_2") (pintype "unspecified+no_connect"))
    )
    (net (code "304") (name "unconnected-(U1-NC-Pad5)") (class "Default")
      (node (ref "U1") (pin "5") (pinfunction "NC_5") (pintype "unspecified+no_connect"))
    )
    (net (code "305") (name "unconnected-(U1-NC-Pad7)") (class "Default")
      (node (ref "U1") (pin "7") (pinfunction "NC_7") (pintype "unspecified+no_connect"))
    )
    (net (code "306") (name "unconnected-(U1-NC-Pad22)") (class "Default")
      (node (ref "U1") (pin "22") (pinfunction "NC_22") (pintype "unspecified+no_connect"))
    )
    (net (code "307") (name "unconnected-(U1-NC-Pad24)") (class "Default")
      (node (ref "U1") (pin "24") (pinfunction "NC_24") (pintype "unspecified+no_connect"))
    )
    (net (code "308") (name "unconnected-(U1-NC-Pad27)") (class "Default")
      (node (ref "U1") (pin "27") (pinfunction "NC_27") (pintype "unspecified+no_connect"))
    )
    (net (code "309") (name "unconnected-(U1-NC-Pad28)") (class "Default")
      (node (ref "U1") (pin "28") (pinfunction "NC_28") (pintype "unspecified+no_connect"))
    )
    (net (code "310") (name "unconnected-(U1-NC-Pad49)") (class "Default")
      (node (ref "U1") (pin "49") (pinfunction "NC_49") (pintype "unspecified+no_connect"))
    )
    (net (code "311") (name "unconnected-(U1-NC-Pad50)") (class "Default")
      (node (ref "U1") (pin "50") (pinfunction "NC_50") (pintype "unspecified+no_connect"))
    )
    (net (code "312") (name "unconnected-(U1-NC-Pad53)") (class "Default")
      (node (ref "U1") (pin "53") (pinfunction "NC_53") (pintype "unspecified+no_connect"))
    )
    (net (code "313") (name "unconnected-(U1-NC-Pad55)") (class "Default")
      (node (ref "U1") (pin "55") (pinfunction "NC_55") (pintype "unspecified+no_connect"))
    )
    (net (code "314") (name "unconnected-(U1-NC-Pad70)") (class "Default")
      (node (ref "U1") (pin "70") (pinfunction "NC_70") (pintype "unspecified+no_connect"))
    )
    (net (code "315") (name "unconnected-(U1-NC-Pad72)") (class "Default")
      (node (ref "U1") (pin "72") (pinfunction "NC_72") (pintype "unspecified+no_connect"))
    )
    (net (code "316") (name "unconnected-(U1-NC-Pad77)") (class "Default")
      (node (ref "U1") (pin "77") (pinfunction "NC_77") (pintype "unspecified+no_connect"))
    )
    (net (code "317") (name "unconnected-(U1-NC-Pad78)") (class "Default")
      (node (ref "U1") (pin "78") (pinfunction "NC_78") (pintype "unspecified+no_connect"))
    )
  )
)
